# ALLModule_v1_0_2025-04-21.net
KiCad netlist of a schematic drawn in EasyEDA Pro
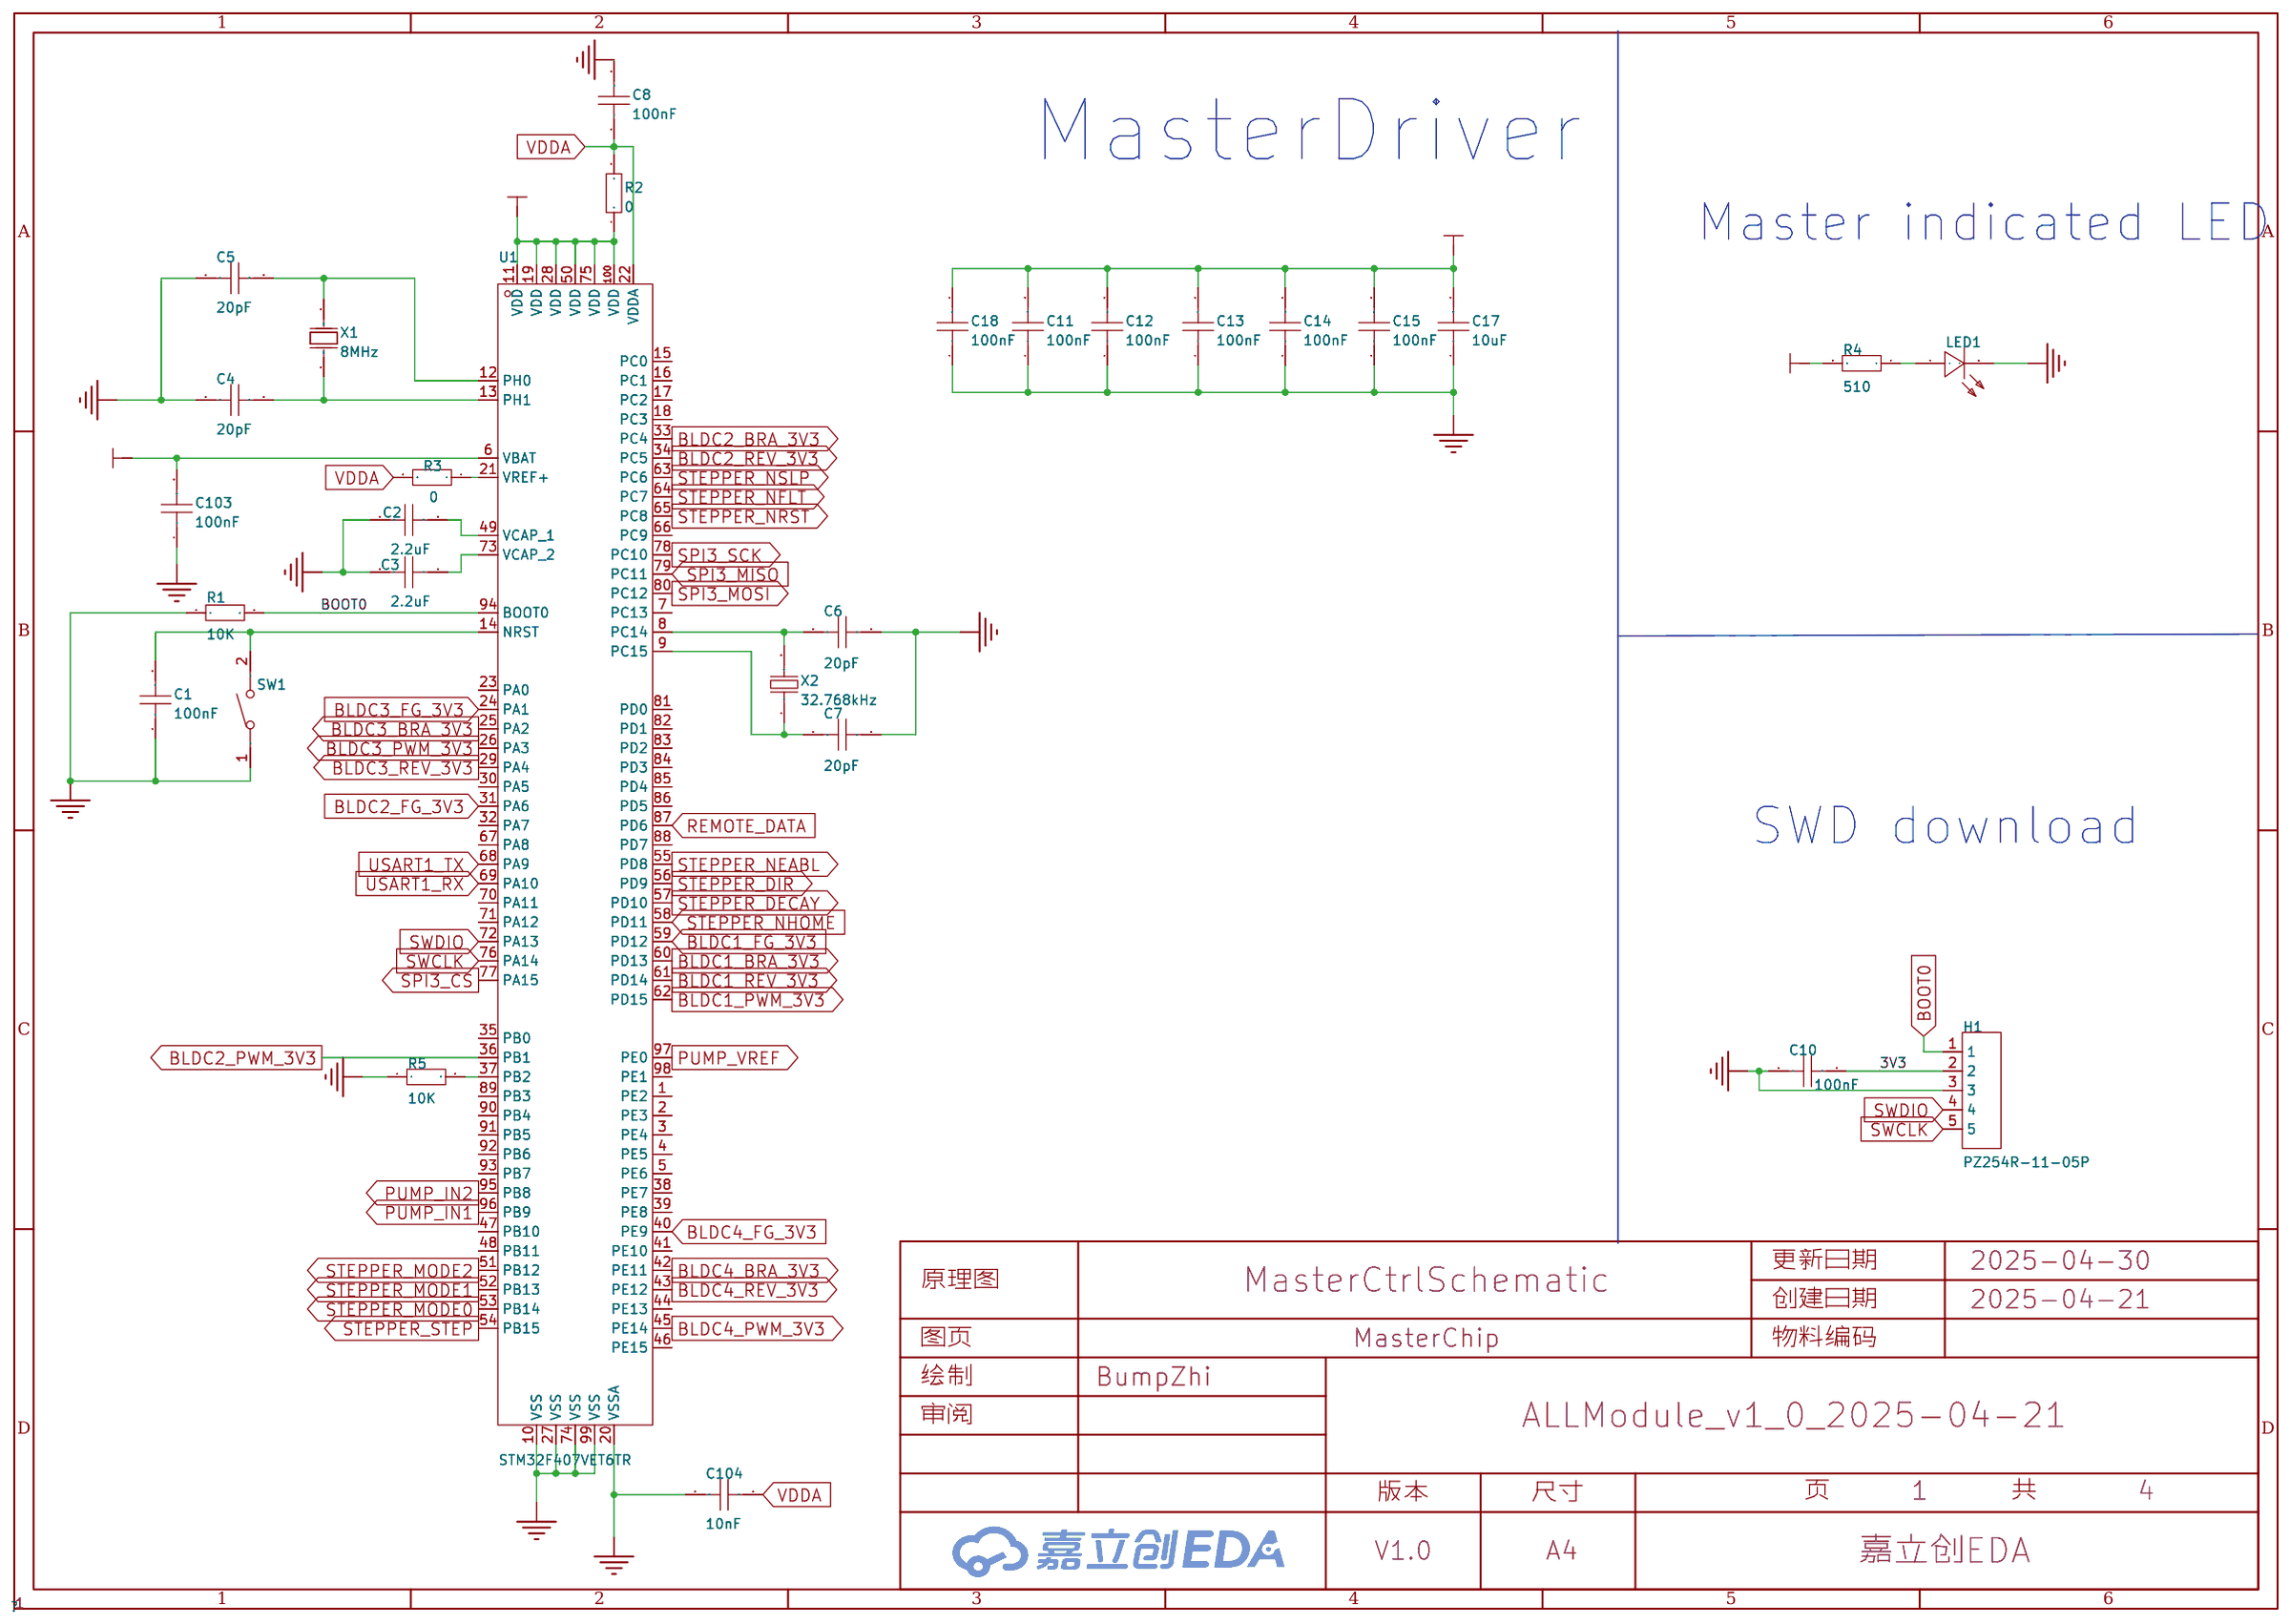
[diagram p0: MasterChip]
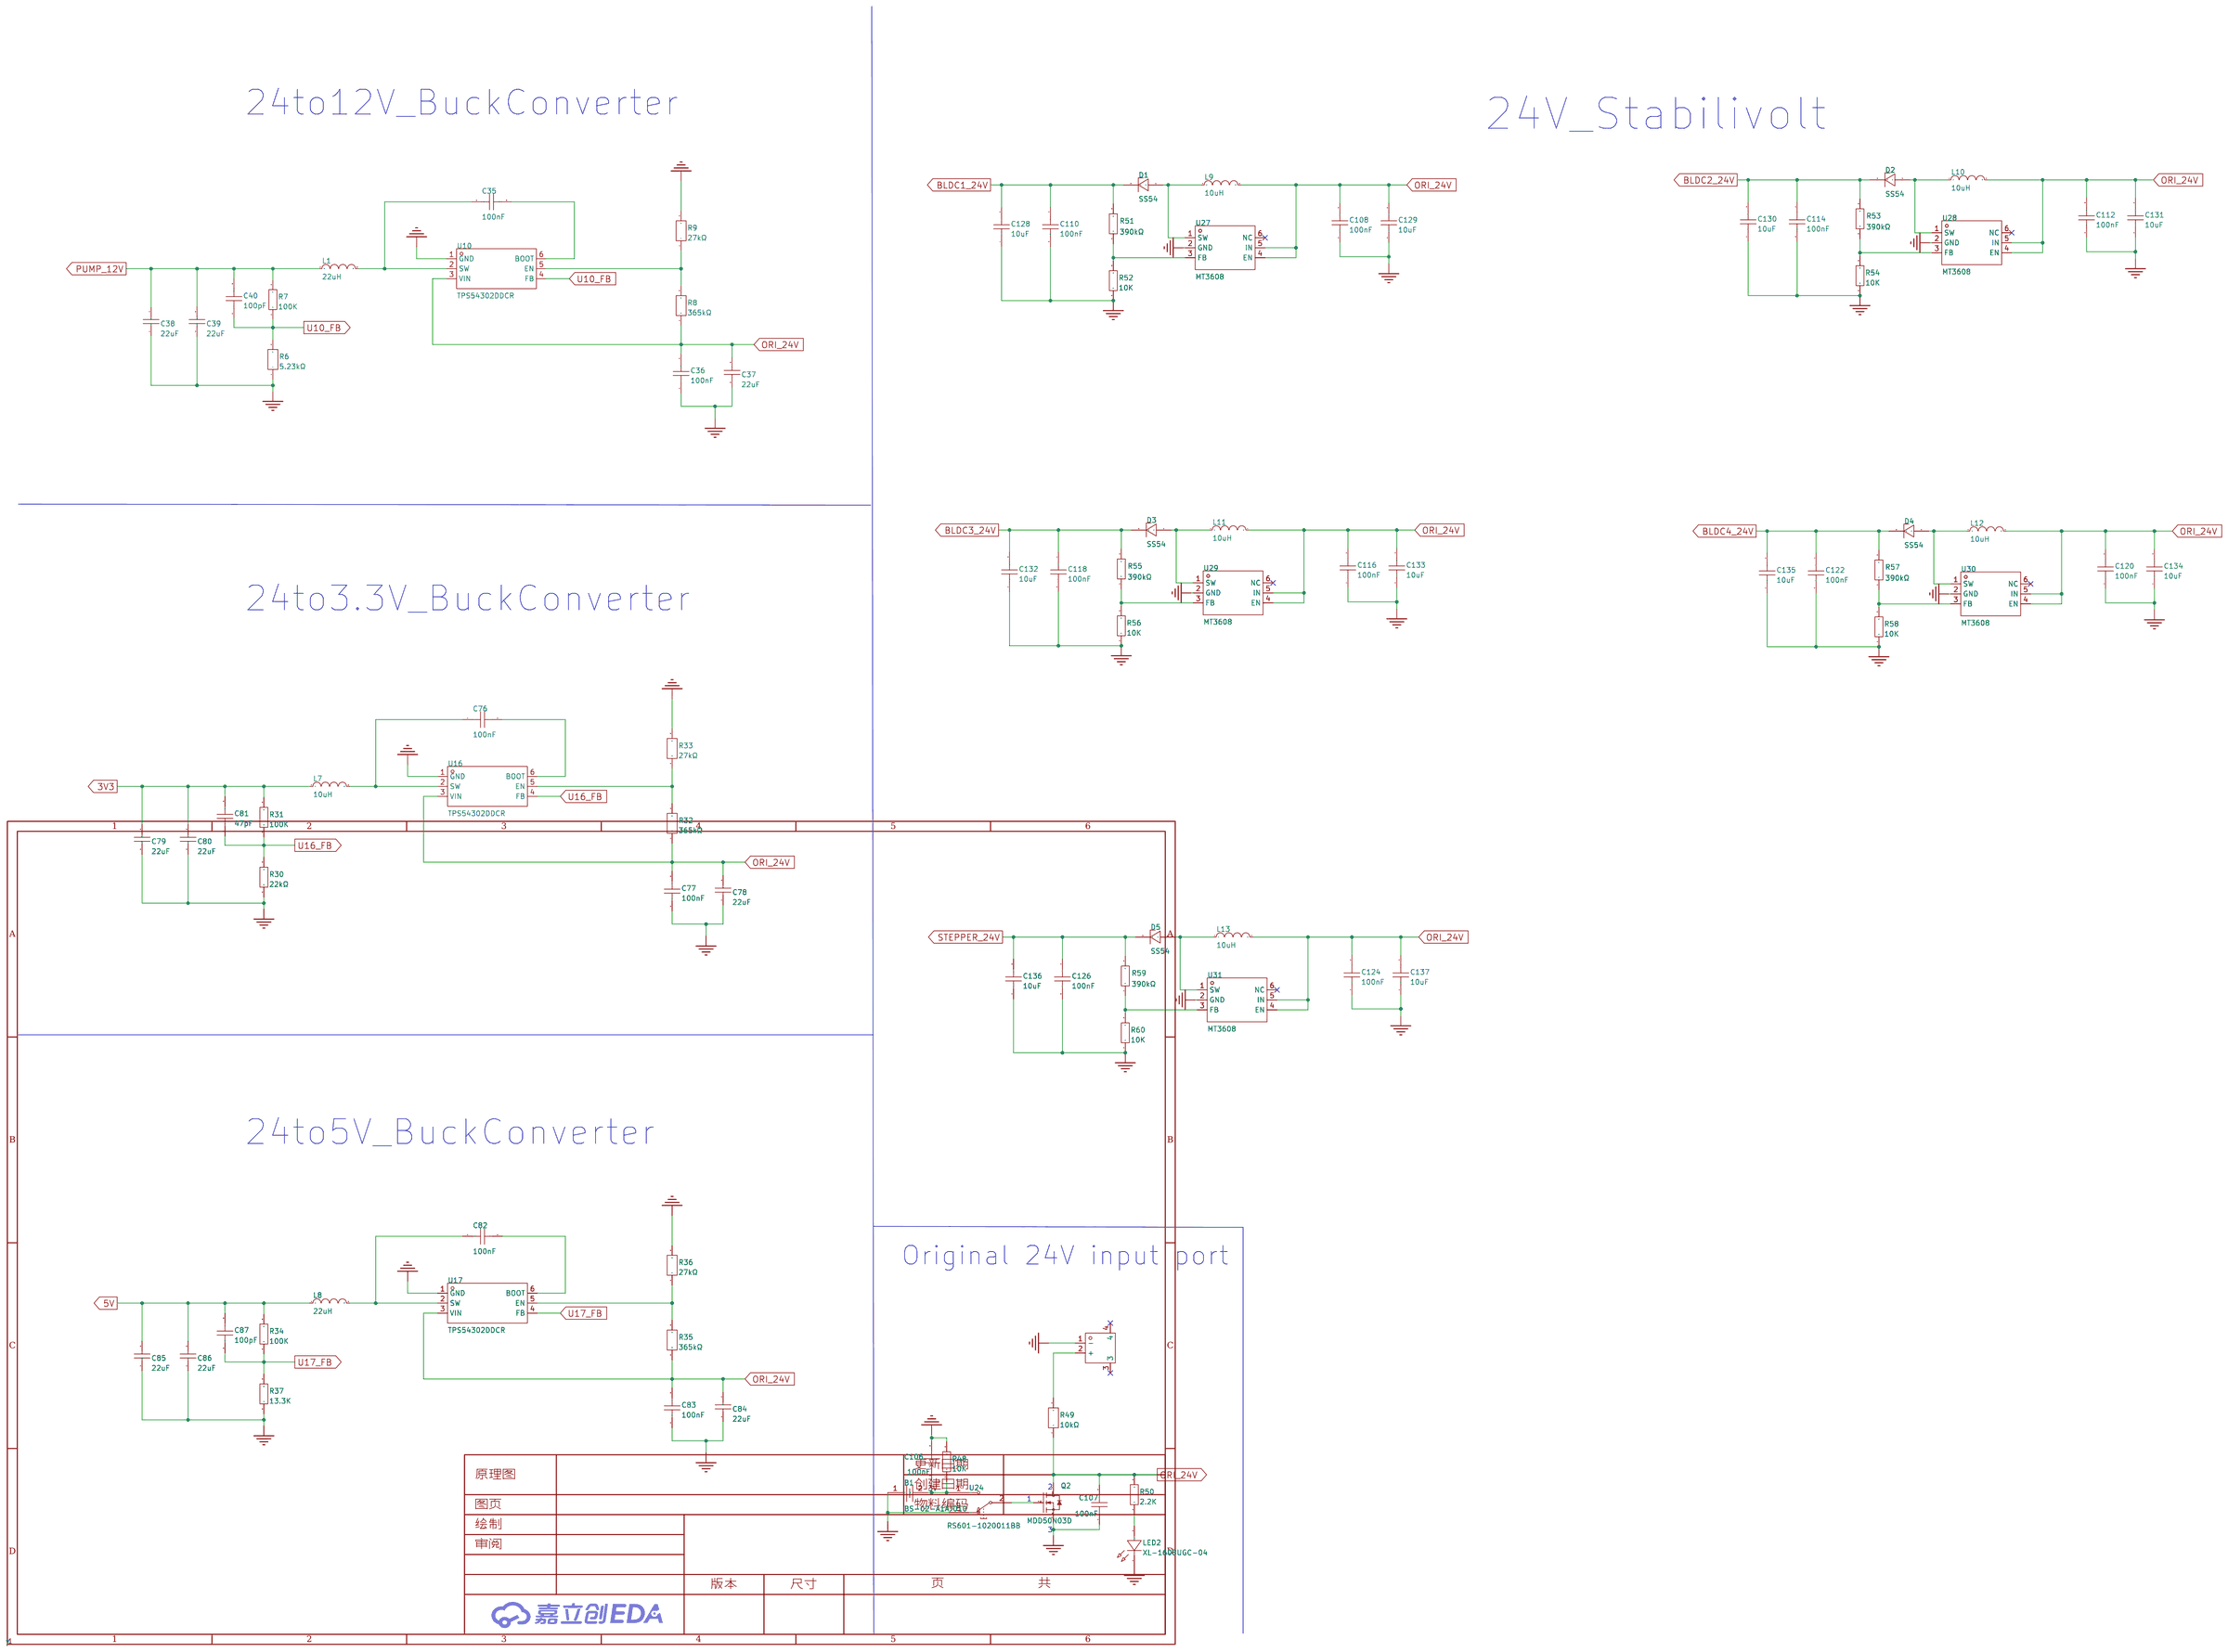
[diagram p1: PowerCtrl]
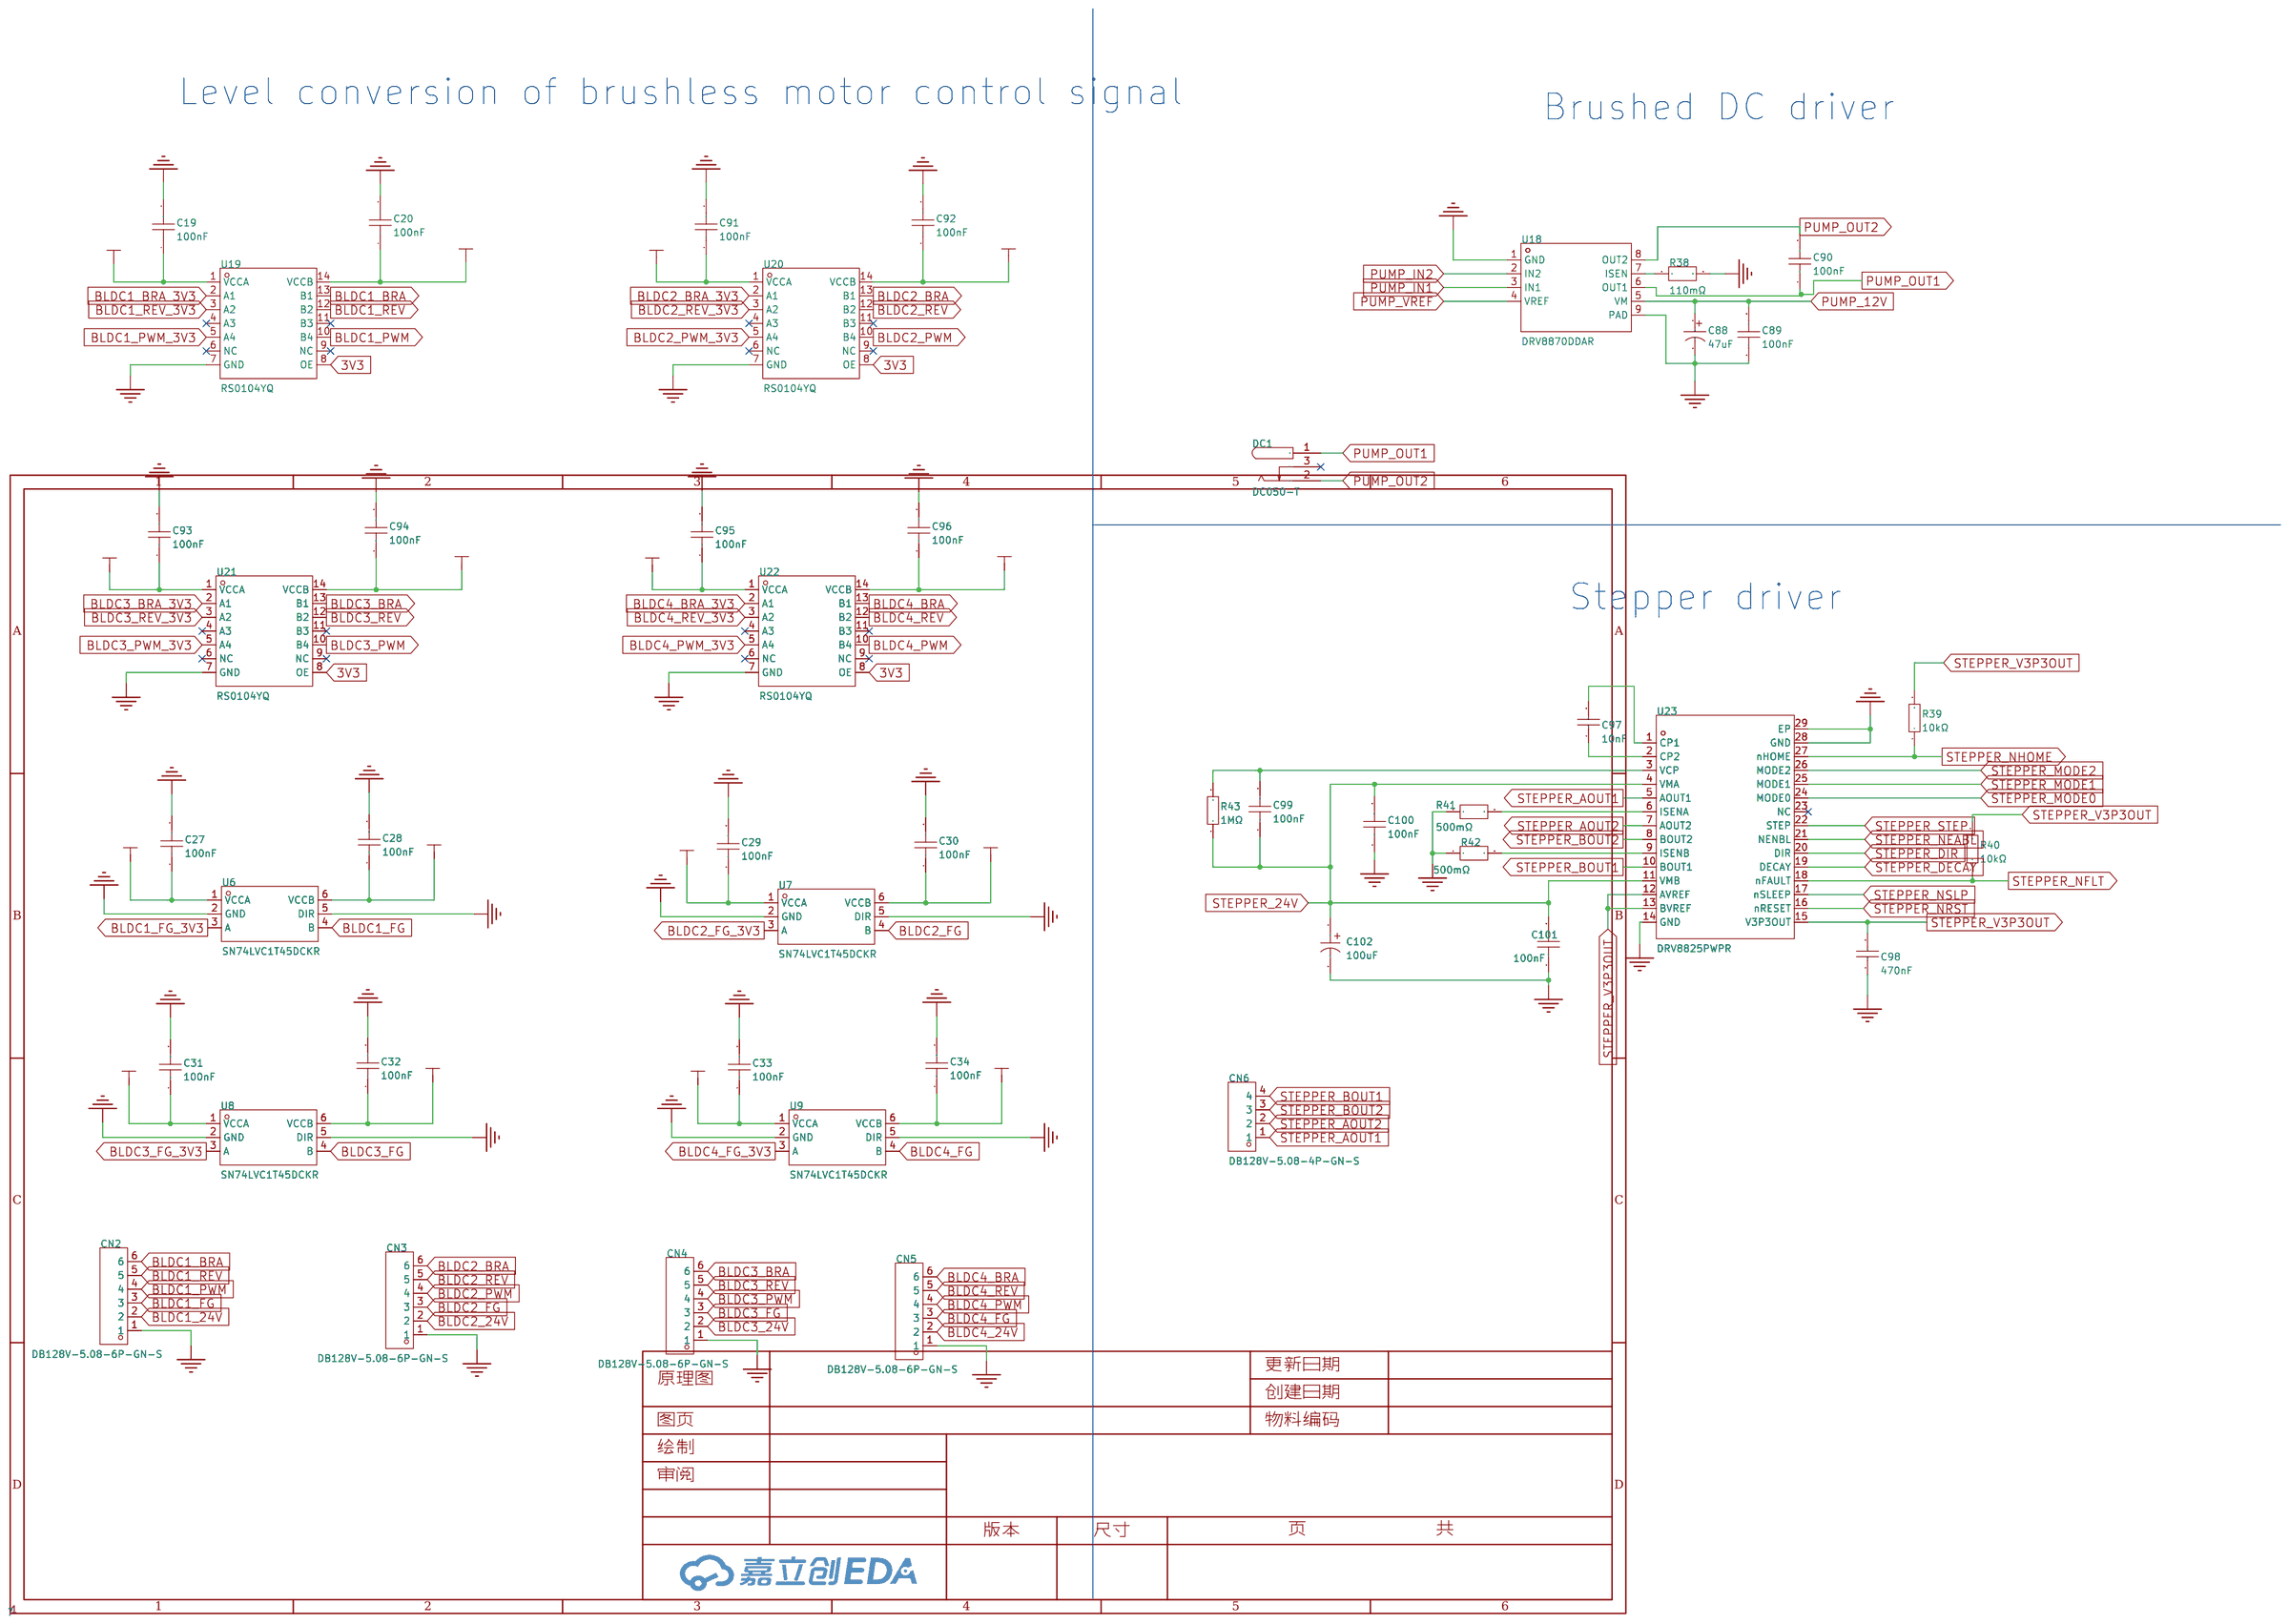
[diagram p2: MotorCtrl]
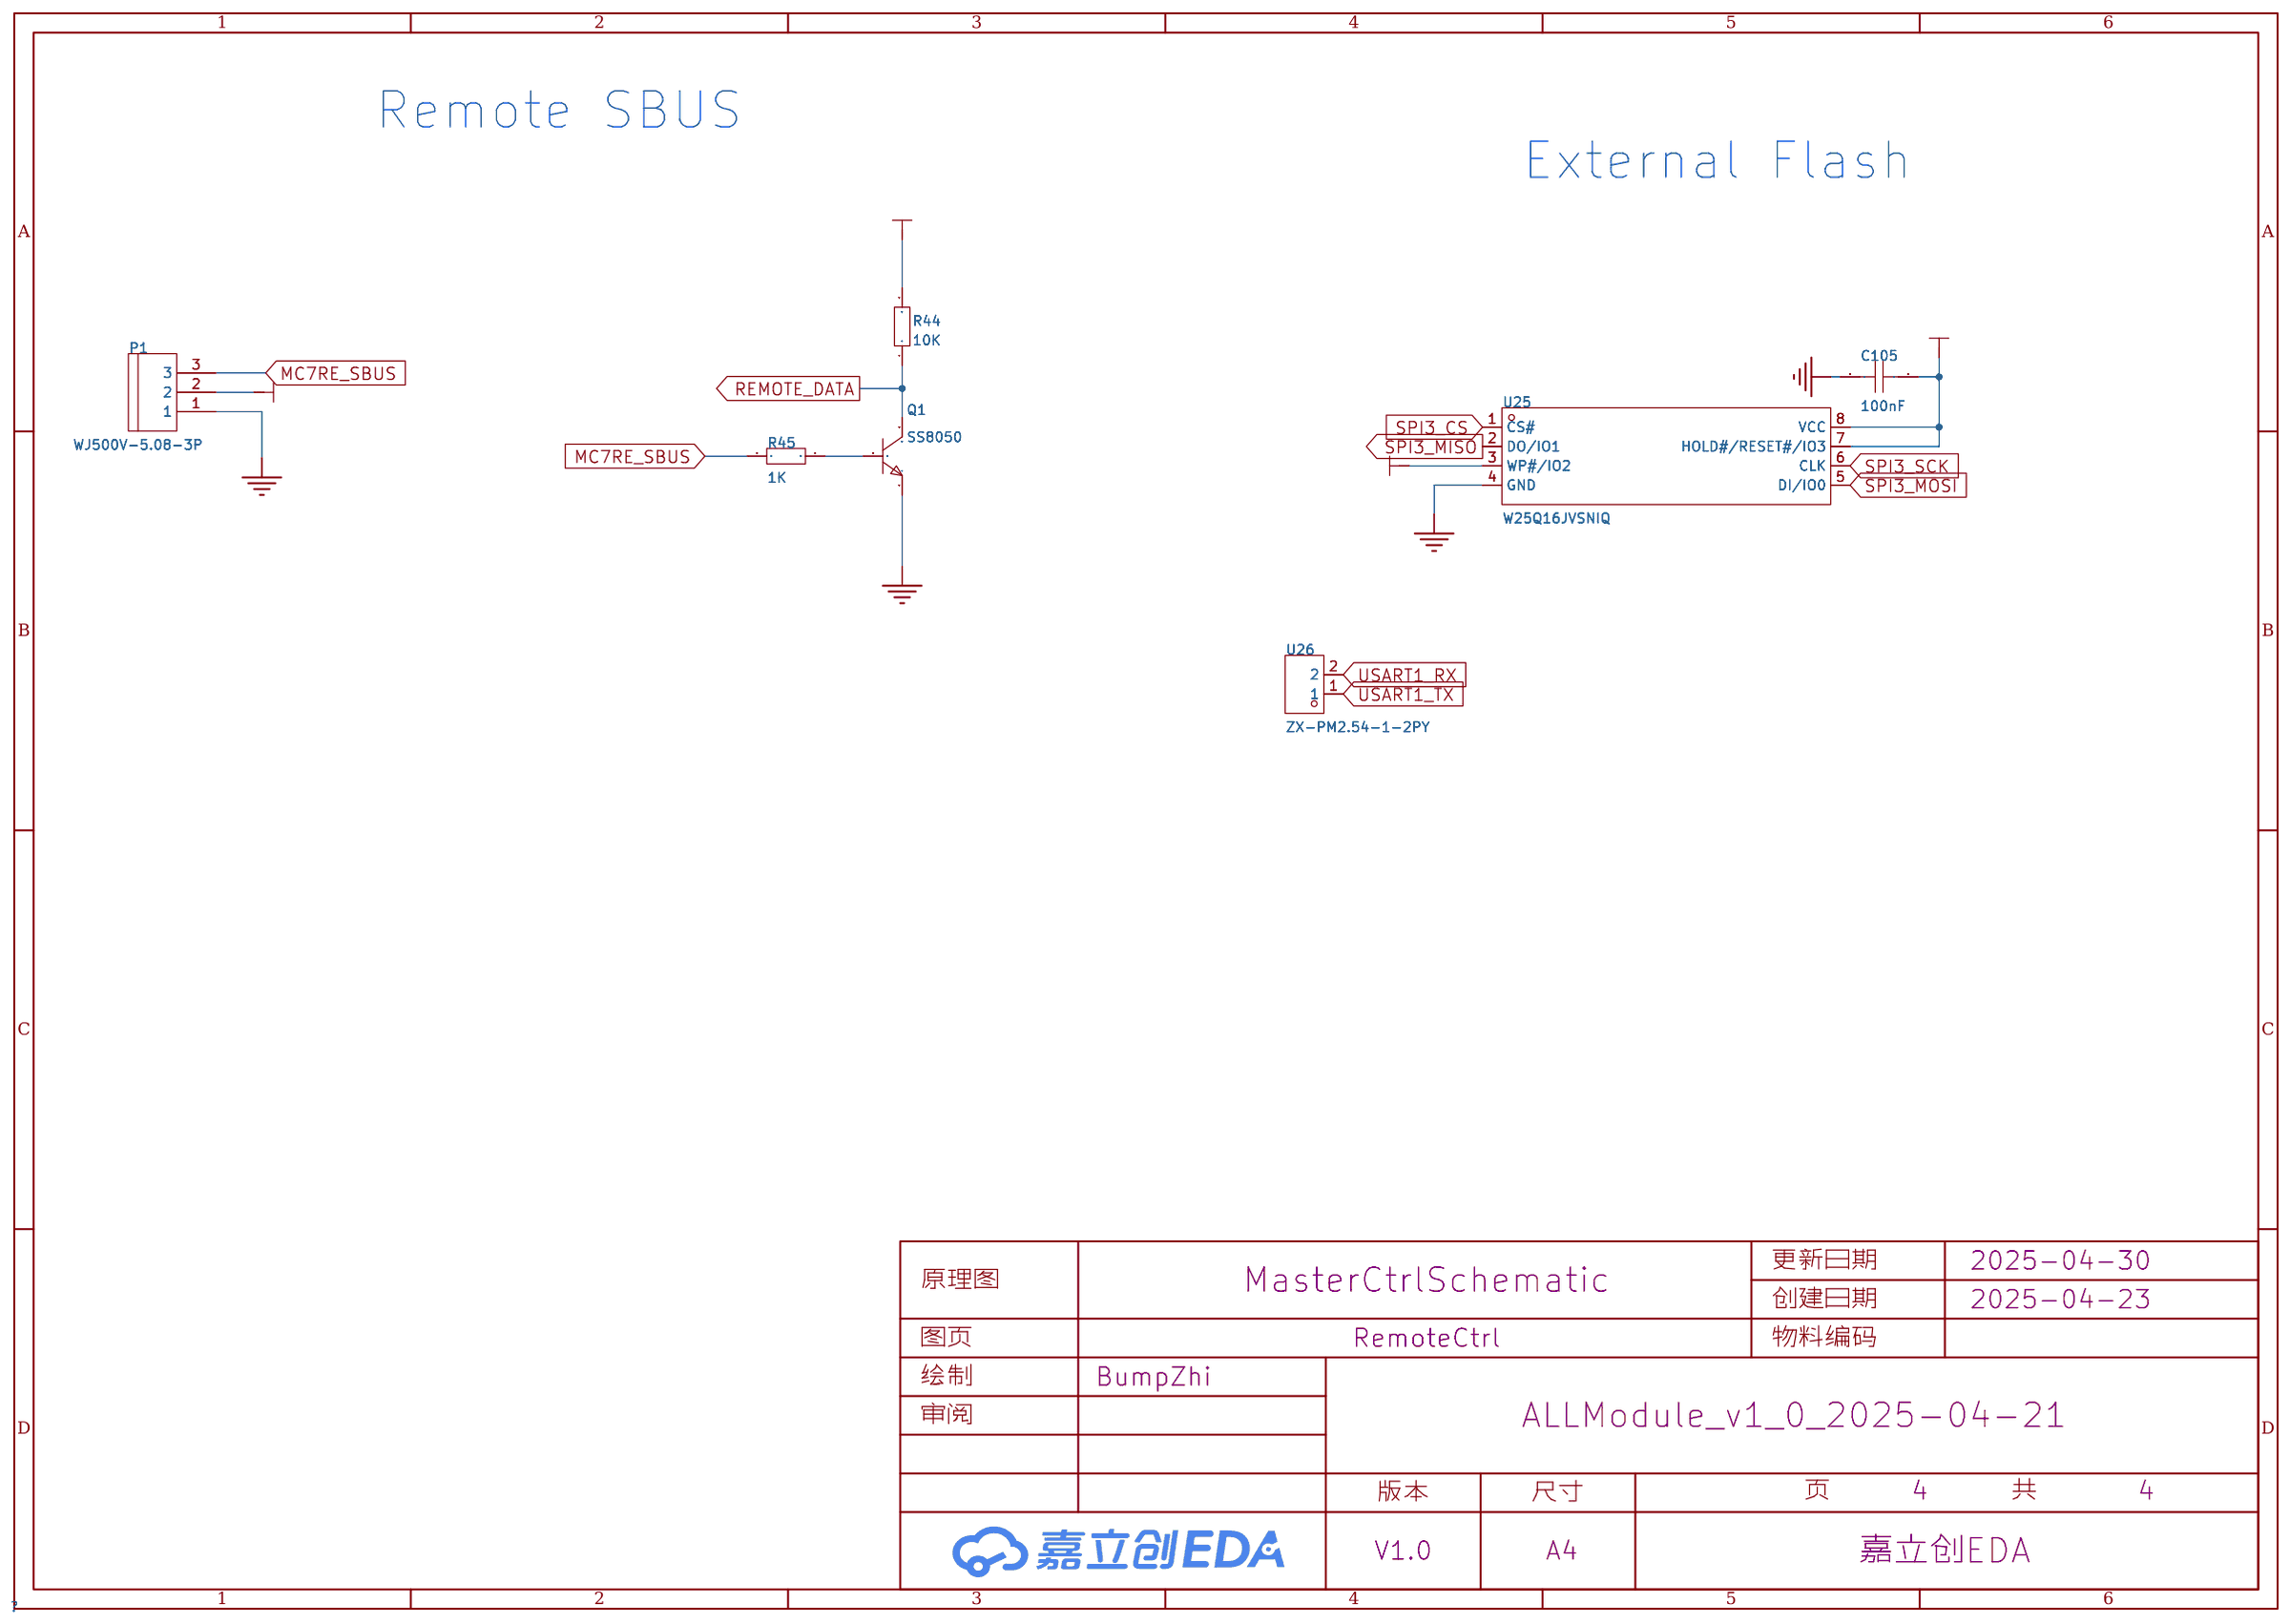
[diagram p3: RemoteCtrl]

(export (version "E")
  (design (tool "Eeschema 10.0.6"))
  (components
    (comp (ref "C1")
      (value "100nF")
      (footprint "easyedapro:C0603")
      (libsource (lib "easyedapro") (part "CapAcitance"))
    )
    (comp (ref "C2")
      (value "2.2uF")
      (footprint "easyedapro:C0603")
      (libsource (lib "easyedapro") (part "CapAcitance"))
    )
    (comp (ref "C3")
      (value "2.2uF")
      (footprint "easyedapro:C0603")
      (libsource (lib "easyedapro") (part "CapAcitance"))
    )
    (comp (ref "C4")
      (value "20pF")
      (footprint "easyedapro:C0603")
      (libsource (lib "easyedapro") (part "CapAcitance"))
    )
    (comp (ref "C5")
      (value "20pF")
      (footprint "easyedapro:C0603")
      (libsource (lib "easyedapro") (part "CapAcitance"))
    )
    (comp (ref "C6")
      (value "20pF")
      (footprint "easyedapro:C0603")
      (libsource (lib "easyedapro") (part "CapAcitance"))
    )
    (comp (ref "C7")
      (value "20pF")
      (footprint "easyedapro:C0603")
      (libsource (lib "easyedapro") (part "CapAcitance"))
    )
    (comp (ref "C8")
      (value "100nF")
      (footprint "easyedapro:C0603")
      (libsource (lib "easyedapro") (part "CapAcitance"))
    )
    (comp (ref "C10")
      (value "100nF")
      (footprint "easyedapro:C0603")
      (libsource (lib "easyedapro") (part "CapAcitance"))
    )
    (comp (ref "C11")
      (value "100nF")
      (footprint "easyedapro:C0603")
      (libsource (lib "easyedapro") (part "CapAcitance"))
    )
    (comp (ref "C12")
      (value "100nF")
      (footprint "easyedapro:C0603")
      (libsource (lib "easyedapro") (part "CapAcitance"))
    )
    (comp (ref "C13")
      (value "100nF")
      (footprint "easyedapro:C0603")
      (libsource (lib "easyedapro") (part "CapAcitance"))
    )
    (comp (ref "C14")
      (value "100nF")
      (footprint "easyedapro:C0603")
      (libsource (lib "easyedapro") (part "CapAcitance"))
    )
    (comp (ref "C15")
      (value "100nF")
      (footprint "easyedapro:C0603")
      (libsource (lib "easyedapro") (part "CapAcitance"))
    )
    (comp (ref "C17")
      (value "10uF")
      (footprint "easyedapro:C0603")
      (libsource (lib "easyedapro") (part "CapAcitance"))
    )
    (comp (ref "C18")
      (value "100nF")
      (footprint "easyedapro:C0603")
      (libsource (lib "easyedapro") (part "CapAcitance"))
    )
    (comp (ref "C103")
      (value "100nF")
      (footprint "easyedapro:C0603")
      (libsource (lib "easyedapro") (part "CapAcitance"))
    )
    (comp (ref "C104")
      (value "10nF")
      (footprint "easyedapro:C0603")
      (libsource (lib "easyedapro") (part "CapAcitance"))
    )
    (comp (ref "H1")
      (value "PZ254R-11-05P")
      (footprint "easyedapro:HDR-TH_5P-P2.54-H-M-W10.4")
      (fields (field (name "Manufacturer") "XFCN(兴飞)"))
      (libsource (lib "easyedapro") (part "PZ254R-11-05P"))
    )
    (comp (ref "LED1")
      (value "SZYY0805R")
      (footprint "easyedapro:LED0805-R-RD")
      (fields (field (name "Manufacturer") "yongyu(永裕光电)"))
      (libsource (lib "easyedapro") (part "SZYY0805R"))
    )
    (comp (ref "R1") (value "10K") (footprint "easyedapro:R0603") (libsource (lib "easyedapro") (part "电阻")))
    (comp (ref "R2") (value "0") (footprint "easyedapro:R0603") (libsource (lib "easyedapro") (part "电阻")))
    (comp (ref "R3") (value "0") (footprint "easyedapro:R0603") (libsource (lib "easyedapro") (part "电阻")))
    (comp (ref "R4") (value "510") (footprint "easyedapro:R0603") (libsource (lib "easyedapro") (part "电阻")))
    (comp (ref "R5") (value "10K") (footprint "easyedapro:R0603") (libsource (lib "easyedapro") (part "电阻")))
    (comp (ref "SW1")
      (value "TS-1088-AR02016")
      (footprint "easyedapro:SW-SMD_L3.9-W3.0-P4.45")
      (fields (field (name "Manufacturer") "XUNPU(讯普)"))
      (libsource (lib "easyedapro") (part "TS-1088-AR02016"))
    )
    (comp (ref "U1")
      (value "STM32F407VET6TR")
      (footprint "easyedapro:LQFP-100_L14.0-W14.0-P0.50-LS16.0-BL")
      (description "CPU内核:ARM-M4;CPU最大主频:168MHz;应用领域:-;")
      (fields (field (name "Manufacturer") "ST(意法半导体)"))
      (libsource (lib "easyedapro") (part "STM32F407VET6TR"))
    )
    (comp (ref "X1")
      (value "8MHz")
      (footprint "easyedapro:CRYSTAL-SMD_L11.5-W4.8-LS12.7")
      (description "晶振类型:贴片晶振;频率:8MHz;常温频差:±20ppm;外接负载电容:20pF;频率稳定度(全温):±30ppm;")
      (fields (field (name "Manufacturer Part") "X49SM8MSD2SC") (field (name "Manufacturer") "YXC(扬兴晶振)"))
      (libsource (lib "easyedapro") (part "X49SM8MSD2SC"))
    )
    (comp (ref "X2")
      (value "32.768kHz")
      (footprint "easyedapro:FC-135R_L3.2-W1.5")
      (description "晶振类型:贴片晶振;频率:32.768kHz;常温频差:±20ppm;负载电容:12.5pF;")
      (fields (field (name "Manufacturer Part") "Q13FC13500004") (field (name "Manufacturer") "EPSON(爱普生)"))
      (libsource (lib "easyedapro") (part "Q13FC1350000400"))
    )
    (comp (ref "B1")
      (value "BS-02-A1AJ010")
      (footprint "easyedapro:BAT-TH_BS-02-A1AJ010")
      (description "连接器类型:电池底座;适用电池规格:CR2032;触头材质:磷青铜;触点电镀:镍;工作温度范围:-25°C~+85°C;")
      (fields (field (name "Manufacturer") "MYOUNG(美阳)"))
      (libsource (lib "easyedapro") (part "BS-02-A1AJ010"))
    )
    (comp (ref "C35")
      (value "100nF")
      (footprint "easyedapro:C0603")
      (libsource (lib "easyedapro") (part "CapAcitance"))
    )
    (comp (ref "C36")
      (value "100nF")
      (footprint "easyedapro:C0603")
      (libsource (lib "easyedapro") (part "CapAcitance"))
    )
    (comp (ref "C37")
      (value "22uF")
      (footprint "easyedapro:C1206")
      (description "容值:22uF;精度:±10%;额定电压:25V;材质(温度系数):X5R;")
      (fields
        (field (name "Manufacturer Part") "CL31A226KAHNNNE")
        (field (name "Manufacturer") "SAMSUNG(三星)")
      )
      (libsource (lib "easyedapro") (part "CL31A226KAHNNNE"))
    )
    (comp (ref "C38")
      (value "22uF")
      (footprint "easyedapro:C1206")
      (description "容值:22uF;精度:±10%;额定电压:25V;材质(温度系数):X5R;")
      (fields
        (field (name "Manufacturer Part") "CL31A226KAHNNNE")
        (field (name "Manufacturer") "SAMSUNG(三星)")
      )
      (libsource (lib "easyedapro") (part "CL31A226KAHNNNE"))
    )
    (comp (ref "C39")
      (value "22uF")
      (footprint "easyedapro:C1206")
      (description "容值:22uF;精度:±10%;额定电压:25V;材质(温度系数):X5R;")
      (fields
        (field (name "Manufacturer Part") "CL31A226KAHNNNE")
        (field (name "Manufacturer") "SAMSUNG(三星)")
      )
      (libsource (lib "easyedapro") (part "CL31A226KAHNNNE"))
    )
    (comp (ref "C40")
      (value "100pF")
      (footprint "easyedapro:C0603")
      (description "容值:100pF;精度:±5%;额定电压:50V;材质(温度系数):NP0;")
      (fields
        (field (name "Manufacturer Part") "CC0603JRNPO9BN101")
        (field (name "Manufacturer") "YAGEO(国巨)")
      )
      (libsource (lib "easyedapro") (part "CC0603JRNPO9BN101"))
    )
    (comp (ref "C76")
      (value "100nF")
      (footprint "easyedapro:C0603")
      (libsource (lib "easyedapro") (part "CapAcitance"))
    )
    (comp (ref "C77")
      (value "100nF")
      (footprint "easyedapro:C0603")
      (libsource (lib "easyedapro") (part "CapAcitance"))
    )
    (comp (ref "C78")
      (value "22uF")
      (footprint "easyedapro:C1206")
      (description "容值:22uF;精度:±10%;额定电压:25V;材质(温度系数):X5R;")
      (fields
        (field (name "Manufacturer Part") "CL31A226KAHNNNE")
        (field (name "Manufacturer") "SAMSUNG(三星)")
      )
      (libsource (lib "easyedapro") (part "CL31A226KAHNNNE"))
    )
    (comp (ref "C79")
      (value "22uF")
      (footprint "easyedapro:C1206")
      (description "容值:22uF;精度:±10%;额定电压:25V;材质(温度系数):X5R;")
      (fields
        (field (name "Manufacturer Part") "CL31A226KAHNNNE")
        (field (name "Manufacturer") "SAMSUNG(三星)")
      )
      (libsource (lib "easyedapro") (part "CL31A226KAHNNNE"))
    )
    (comp (ref "C80")
      (value "22uF")
      (footprint "easyedapro:C1206")
      (description "容值:22uF;精度:±10%;额定电压:25V;材质(温度系数):X5R;")
      (fields
        (field (name "Manufacturer Part") "CL31A226KAHNNNE")
        (field (name "Manufacturer") "SAMSUNG(三星)")
      )
      (libsource (lib "easyedapro") (part "CL31A226KAHNNNE"))
    )
    (comp (ref "C81")
      (value "47pF")
      (footprint "easyedapro:C0603")
      (description "容值:100pF;精度:±5%;额定电压:50V;材质(温度系数):NP0;")
      (fields
        (field (name "Manufacturer Part") "CC0603JRNPO9BN101")
        (field (name "Manufacturer") "YAGEO(国巨)")
      )
      (libsource (lib "easyedapro") (part "CC0603JRNPO9BN101"))
    )
    (comp (ref "C82")
      (value "100nF")
      (footprint "easyedapro:C0603")
      (libsource (lib "easyedapro") (part "CapAcitance"))
    )
    (comp (ref "C83")
      (value "100nF")
      (footprint "easyedapro:C0603")
      (libsource (lib "easyedapro") (part "CapAcitance"))
    )
    (comp (ref "C84")
      (value "22uF")
      (footprint "easyedapro:C1206")
      (description "容值:22uF;精度:±10%;额定电压:25V;材质(温度系数):X5R;")
      (fields
        (field (name "Manufacturer Part") "CL31A226KAHNNNE")
        (field (name "Manufacturer") "SAMSUNG(三星)")
      )
      (libsource (lib "easyedapro") (part "CL31A226KAHNNNE"))
    )
    (comp (ref "C85")
      (value "22uF")
      (footprint "easyedapro:C1206")
      (description "容值:22uF;精度:±10%;额定电压:25V;材质(温度系数):X5R;")
      (fields
        (field (name "Manufacturer Part") "CL31A226KAHNNNE")
        (field (name "Manufacturer") "SAMSUNG(三星)")
      )
      (libsource (lib "easyedapro") (part "CL31A226KAHNNNE"))
    )
    (comp (ref "C86")
      (value "22uF")
      (footprint "easyedapro:C1206")
      (description "容值:22uF;精度:±10%;额定电压:25V;材质(温度系数):X5R;")
      (fields
        (field (name "Manufacturer Part") "CL31A226KAHNNNE")
        (field (name "Manufacturer") "SAMSUNG(三星)")
      )
      (libsource (lib "easyedapro") (part "CL31A226KAHNNNE"))
    )
    (comp (ref "C87")
      (value "100pF")
      (footprint "easyedapro:C0603")
      (description "容值:100pF;精度:±5%;额定电压:50V;材质(温度系数):NP0;")
      (fields
        (field (name "Manufacturer Part") "CC0603JRNPO9BN101")
        (field (name "Manufacturer") "YAGEO(国巨)")
      )
      (libsource (lib "easyedapro") (part "CC0603JRNPO9BN101"))
    )
    (comp (ref "C106")
      (value "100nF")
      (footprint "easyedapro:C0603")
      (libsource (lib "easyedapro") (part "CapAcitance"))
    )
    (comp (ref "C107")
      (value "100nF")
      (footprint "easyedapro:C0603")
      (libsource (lib "easyedapro") (part "CapAcitance"))
    )
    (comp (ref "C108")
      (value "100nF")
      (footprint "easyedapro:C0603")
      (libsource (lib "easyedapro") (part "CapAcitance"))
    )
    (comp (ref "C110")
      (value "100nF")
      (footprint "easyedapro:C0603")
      (libsource (lib "easyedapro") (part "CapAcitance"))
    )
    (comp (ref "C112")
      (value "100nF")
      (footprint "easyedapro:C0603")
      (libsource (lib "easyedapro") (part "CapAcitance"))
    )
    (comp (ref "C114")
      (value "100nF")
      (footprint "easyedapro:C0603")
      (libsource (lib "easyedapro") (part "CapAcitance"))
    )
    (comp (ref "C116")
      (value "100nF")
      (footprint "easyedapro:C0603")
      (libsource (lib "easyedapro") (part "CapAcitance"))
    )
    (comp (ref "C118")
      (value "100nF")
      (footprint "easyedapro:C0603")
      (libsource (lib "easyedapro") (part "CapAcitance"))
    )
    (comp (ref "C120")
      (value "100nF")
      (footprint "easyedapro:C0603")
      (libsource (lib "easyedapro") (part "CapAcitance"))
    )
    (comp (ref "C122")
      (value "100nF")
      (footprint "easyedapro:C0603")
      (libsource (lib "easyedapro") (part "CapAcitance"))
    )
    (comp (ref "C124")
      (value "100nF")
      (footprint "easyedapro:C0603")
      (libsource (lib "easyedapro") (part "CapAcitance"))
    )
    (comp (ref "C126")
      (value "100nF")
      (footprint "easyedapro:C0603")
      (libsource (lib "easyedapro") (part "CapAcitance"))
    )
    (comp (ref "C128")
      (value "10uF")
      (footprint "easyedapro:C1206")
      (description "容值:10uF;精度:±10%;额定电压:50V;温度系数:X5R;")
      (fields
        (field (name "Manufacturer Part") "HGC1206R5106K500NSPJ")
        (field (name "Manufacturer") "Chinocera(华瓷)")
      )
      (libsource (lib "easyedapro") (part "HGC1206R5106K500NSPJ"))
    )
    (comp (ref "C129")
      (value "10uF")
      (footprint "easyedapro:C1206")
      (description "容值:10uF;精度:±10%;额定电压:50V;温度系数:X5R;")
      (fields
        (field (name "Manufacturer Part") "HGC1206R5106K500NSPJ")
        (field (name "Manufacturer") "Chinocera(华瓷)")
      )
      (libsource (lib "easyedapro") (part "HGC1206R5106K500NSPJ"))
    )
    (comp (ref "C130")
      (value "10uF")
      (footprint "easyedapro:C1206")
      (description "容值:10uF;精度:±10%;额定电压:50V;温度系数:X5R;")
      (fields
        (field (name "Manufacturer Part") "HGC1206R5106K500NSPJ")
        (field (name "Manufacturer") "Chinocera(华瓷)")
      )
      (libsource (lib "easyedapro") (part "HGC1206R5106K500NSPJ"))
    )
    (comp (ref "C131")
      (value "10uF")
      (footprint "easyedapro:C1206")
      (description "容值:10uF;精度:±10%;额定电压:50V;温度系数:X5R;")
      (fields
        (field (name "Manufacturer Part") "HGC1206R5106K500NSPJ")
        (field (name "Manufacturer") "Chinocera(华瓷)")
      )
      (libsource (lib "easyedapro") (part "HGC1206R5106K500NSPJ"))
    )
    (comp (ref "C132")
      (value "10uF")
      (footprint "easyedapro:C1206")
      (description "容值:10uF;精度:±10%;额定电压:50V;温度系数:X5R;")
      (fields
        (field (name "Manufacturer Part") "HGC1206R5106K500NSPJ")
        (field (name "Manufacturer") "Chinocera(华瓷)")
      )
      (libsource (lib "easyedapro") (part "HGC1206R5106K500NSPJ"))
    )
    (comp (ref "C133")
      (value "10uF")
      (footprint "easyedapro:C1206")
      (description "容值:10uF;精度:±10%;额定电压:50V;温度系数:X5R;")
      (fields
        (field (name "Manufacturer Part") "HGC1206R5106K500NSPJ")
        (field (name "Manufacturer") "Chinocera(华瓷)")
      )
      (libsource (lib "easyedapro") (part "HGC1206R5106K500NSPJ"))
    )
    (comp (ref "C134")
      (value "10uF")
      (footprint "easyedapro:C1206")
      (description "容值:10uF;精度:±10%;额定电压:50V;温度系数:X5R;")
      (fields
        (field (name "Manufacturer Part") "HGC1206R5106K500NSPJ")
        (field (name "Manufacturer") "Chinocera(华瓷)")
      )
      (libsource (lib "easyedapro") (part "HGC1206R5106K500NSPJ"))
    )
    (comp (ref "C135")
      (value "10uF")
      (footprint "easyedapro:C1206")
      (description "容值:10uF;精度:±10%;额定电压:50V;温度系数:X5R;")
      (fields
        (field (name "Manufacturer Part") "HGC1206R5106K500NSPJ")
        (field (name "Manufacturer") "Chinocera(华瓷)")
      )
      (libsource (lib "easyedapro") (part "HGC1206R5106K500NSPJ"))
    )
    (comp (ref "C136")
      (value "10uF")
      (footprint "easyedapro:C1206")
      (description "容值:10uF;精度:±10%;额定电压:50V;温度系数:X5R;")
      (fields
        (field (name "Manufacturer Part") "HGC1206R5106K500NSPJ")
        (field (name "Manufacturer") "Chinocera(华瓷)")
      )
      (libsource (lib "easyedapro") (part "HGC1206R5106K500NSPJ"))
    )
    (comp (ref "C137")
      (value "10uF")
      (footprint "easyedapro:C1206")
      (description "容值:10uF;精度:±10%;额定电压:50V;温度系数:X5R;")
      (fields
        (field (name "Manufacturer Part") "HGC1206R5106K500NSPJ")
        (field (name "Manufacturer") "Chinocera(华瓷)")
      )
      (libsource (lib "easyedapro") (part "HGC1206R5106K500NSPJ"))
    )
    (comp (ref "CN1")
      (value "XT60PW-M")
      (footprint "easyedapro:CONN-TH_XT60PW-M")
      (description "类别:-;类型1:-;")
      (fields (field (name "Manufacturer") "AMASS(艾迈斯)"))
      (libsource (lib "easyedapro") (part "XT60PW-M"))
    )
    (comp (ref "D1")
      (value "SS54")
      (footprint "easyedapro:SMA_L4.3-W2.6-LS5.0-FD")
      (description "二极管配置:独立式;正向压降(Vf):550mV@5.0A;直流反向耐压(Vr):40V;整流电流:5A;")
      (fields (field (name "Manufacturer") "宏迦橙"))
      (libsource (lib "easyedapro") (part "SS54_C7420369"))
    )
    (comp (ref "D2")
      (value "SS54")
      (footprint "easyedapro:SMA_L4.3-W2.6-LS5.0-FD")
      (description "二极管配置:独立式;正向压降(Vf):550mV@5.0A;直流反向耐压(Vr):40V;整流电流:5A;")
      (fields (field (name "Manufacturer") "宏迦橙"))
      (libsource (lib "easyedapro") (part "SS54_C7420369"))
    )
    (comp (ref "D3")
      (value "SS54")
      (footprint "easyedapro:SMA_L4.3-W2.6-LS5.0-FD")
      (description "二极管配置:独立式;正向压降(Vf):550mV@5.0A;直流反向耐压(Vr):40V;整流电流:5A;")
      (fields (field (name "Manufacturer") "宏迦橙"))
      (libsource (lib "easyedapro") (part "SS54_C7420369"))
    )
    (comp (ref "D4")
      (value "SS54")
      (footprint "easyedapro:SMA_L4.3-W2.6-LS5.0-FD")
      (description "二极管配置:独立式;正向压降(Vf):550mV@5.0A;直流反向耐压(Vr):40V;整流电流:5A;")
      (fields (field (name "Manufacturer") "宏迦橙"))
      (libsource (lib "easyedapro") (part "SS54_C7420369"))
    )
    (comp (ref "D5")
      (value "SS54")
      (footprint "easyedapro:SMA_L4.3-W2.6-LS5.0-FD")
      (description "二极管配置:独立式;正向压降(Vf):550mV@5.0A;直流反向耐压(Vr):40V;整流电流:5A;")
      (fields (field (name "Manufacturer") "宏迦橙"))
      (libsource (lib "easyedapro") (part "SS54_C7420369"))
    )
    (comp (ref "L1")
      (value "22uH")
      (footprint "easyedapro:IND-SMD_L7.0-W6.6_FXL0630")
      (description "电感值:22uH;精度:±20%;额定电流:2.5A;饱和电流(Isat):3A;类型:一体成型电感;")
      (fields (field (name "Manufacturer Part") "FXL0630-220-M") (field (name "Manufacturer") "cjiang(长江微电)"))
      (libsource (lib "easyedapro") (part "FXL0630-220-M"))
    )
    (comp (ref "L7")
      (value "10uH")
      (footprint "easyedapro:IND-SMD_L7.3-W6.8")
      (description "电感值:10uH;精度:±20%;额定电流:4.5A;饱和电流(Isat):5.5A;类型:一体成型电感;")
      (fields (field (name "Manufacturer Part") "FXL0630-100-M") (field (name "Manufacturer") "cjiang(长江微电)"))
      (libsource (lib "easyedapro") (part "FXL0630-100-M"))
    )
    (comp (ref "L8")
      (value "22uH")
      (footprint "easyedapro:IND-SMD_L7.3-W6.8")
      (description "电感值:10uH;精度:±20%;额定电流:4.5A;饱和电流(Isat):5.5A;类型:一体成型电感;")
      (fields (field (name "Manufacturer Part") "FXL0630-100-M") (field (name "Manufacturer") "cjiang(长江微电)"))
      (libsource (lib "easyedapro") (part "FXL0630-100-M"))
    )
    (comp (ref "L9")
      (value "10uH")
      (footprint "easyedapro:IND-SMD_L7.3-W6.8")
      (description "电感值:10uH;精度:±20%;额定电流:4.5A;饱和电流(Isat):5.5A;类型:一体成型电感;")
      (fields (field (name "Manufacturer Part") "FXL0630-100-M") (field (name "Manufacturer") "cjiang(长江微电)"))
      (libsource (lib "easyedapro") (part "FXL0630-100-M"))
    )
    (comp (ref "L10")
      (value "10uH")
      (footprint "easyedapro:IND-SMD_L7.3-W6.8")
      (description "电感值:10uH;精度:±20%;额定电流:4.5A;饱和电流(Isat):5.5A;类型:一体成型电感;")
      (fields (field (name "Manufacturer Part") "FXL0630-100-M") (field (name "Manufacturer") "cjiang(长江微电)"))
      (libsource (lib "easyedapro") (part "FXL0630-100-M"))
    )
    (comp (ref "L11")
      (value "10uH")
      (footprint "easyedapro:IND-SMD_L7.3-W6.8")
      (description "电感值:10uH;精度:±20%;额定电流:4.5A;饱和电流(Isat):5.5A;类型:一体成型电感;")
      (fields (field (name "Manufacturer Part") "FXL0630-100-M") (field (name "Manufacturer") "cjiang(长江微电)"))
      (libsource (lib "easyedapro") (part "FXL0630-100-M"))
    )
    (comp (ref "L12")
      (value "10uH")
      (footprint "easyedapro:IND-SMD_L7.3-W6.8")
      (description "电感值:10uH;精度:±20%;额定电流:4.5A;饱和电流(Isat):5.5A;类型:一体成型电感;")
      (fields (field (name "Manufacturer Part") "FXL0630-100-M") (field (name "Manufacturer") "cjiang(长江微电)"))
      (libsource (lib "easyedapro") (part "FXL0630-100-M"))
    )
    (comp (ref "L13")
      (value "10uH")
      (footprint "easyedapro:IND-SMD_L7.3-W6.8")
      (description "电感值:10uH;精度:±20%;额定电流:4.5A;饱和电流(Isat):5.5A;类型:一体成型电感;")
      (fields (field (name "Manufacturer Part") "FXL0630-100-M") (field (name "Manufacturer") "cjiang(长江微电)"))
      (libsource (lib "easyedapro") (part "FXL0630-100-M"))
    )
    (comp (ref "LED2")
      (value "XL-1608UGC-04")
      (footprint "easyedapro:LED0603-RD_GREEN")
      (fields (field (name "Manufacturer") "XINGLIGHT(成兴光)"))
      (libsource (lib "easyedapro") (part "XL-1608UGC-04"))
    )
    (comp (ref "Q2")
      (value "MDD50N03D")
      (footprint "easyedapro:TO-252-2_L6.6-W6.1-P4.57-LS9.9-BR-CW")
      (fields (field (name "Manufacturer") "MDD(辰达半导体)"))
      (libsource (lib "easyedapro") (part "MDD50N03D"))
    )
    (comp (ref "R6")
      (value "5.23kΩ")
      (footprint "easyedapro:R0805")
      (description "电阻类型:厚膜电阻;阻值:5.23kΩ;精度:±1%;功率:125mW;工作电压:150V;温度系数:±100ppm/°C;")
      (fields (field (name "Manufacturer Part") "FRC0805F5231TS") (field (name "Manufacturer") "FOJAN(富捷)"))
      (libsource (lib "easyedapro") (part "FRC0805F5231TS"))
    )
    (comp (ref "R7") (value "100K") (footprint "easyedapro:R0603") (libsource (lib "easyedapro") (part "电阻")))
    (comp (ref "R8")
      (value "365kΩ")
      (footprint "easyedapro:R1210")
      (description "电阻类型:厚膜电阻;阻值:365kΩ;精度:±1%;功率:500mW;最大工作电压:200V;温度系数:±100ppm/°C;")
      (fields (field (name "Manufacturer Part") "AC1210FR-07365KL") (field (name "Manufacturer") "YAGEO(国巨)"))
      (libsource (lib "easyedapro") (part "AC1210FR-07365KL"))
    )
    (comp (ref "R9")
      (value "27kΩ")
      (footprint "easyedapro:R0603")
      (description "电阻类型:厚膜电阻;阻值:27kΩ;精度:±1%;功率:100mW;工作电压:75V;温度系数:±100ppm/°C;")
      (fields (field (name "Manufacturer Part") "FRC0603F2702TS") (field (name "Manufacturer") "FOJAN(富捷)"))
      (libsource (lib "easyedapro") (part "FRC0603F2702TS"))
    )
    (comp (ref "R30")
      (value "22kΩ")
      (footprint "easyedapro:R0603")
      (description "电阻类型:厚膜电阻;阻值:22kΩ;精度:±1%;功率:100mW;最大工作电压:75V;温度系数:±100ppm/°C;")
      (fields
        (field (name "Manufacturer Part") "0603WAF2202T5E")
        (field (name "Manufacturer") "UNI-ROYAL(厚声)")
      )
      (libsource (lib "easyedapro") (part "0603WAF2202T5E"))
    )
    (comp (ref "R31")
      (value "100K")
      (footprint "easyedapro:R0603")
      (libsource (lib "easyedapro") (part "电阻"))
    )
    (comp (ref "R32")
      (value "365kΩ")
      (footprint "easyedapro:R1210")
      (description "电阻类型:厚膜电阻;阻值:365kΩ;精度:±1%;功率:500mW;最大工作电压:200V;温度系数:±100ppm/°C;")
      (fields (field (name "Manufacturer Part") "AC1210FR-07365KL") (field (name "Manufacturer") "YAGEO(国巨)"))
      (libsource (lib "easyedapro") (part "AC1210FR-07365KL"))
    )
    (comp (ref "R33")
      (value "27kΩ")
      (footprint "easyedapro:R0603")
      (description "电阻类型:厚膜电阻;阻值:27kΩ;精度:±1%;功率:100mW;工作电压:75V;温度系数:±100ppm/°C;")
      (fields (field (name "Manufacturer Part") "FRC0603F2702TS") (field (name "Manufacturer") "FOJAN(富捷)"))
      (libsource (lib "easyedapro") (part "FRC0603F2702TS"))
    )
    (comp (ref "R34")
      (value "100K")
      (footprint "easyedapro:R0603")
      (libsource (lib "easyedapro") (part "电阻"))
    )
    (comp (ref "R35")
      (value "365kΩ")
      (footprint "easyedapro:R1210")
      (description "电阻类型:厚膜电阻;阻值:365kΩ;精度:±1%;功率:500mW;最大工作电压:200V;温度系数:±100ppm/°C;")
      (fields (field (name "Manufacturer Part") "AC1210FR-07365KL") (field (name "Manufacturer") "YAGEO(国巨)"))
      (libsource (lib "easyedapro") (part "AC1210FR-07365KL"))
    )
    (comp (ref "R36")
      (value "27kΩ")
      (footprint "easyedapro:R0603")
      (description "电阻类型:厚膜电阻;阻值:27kΩ;精度:±1%;功率:100mW;工作电压:75V;温度系数:±100ppm/°C;")
      (fields (field (name "Manufacturer Part") "FRC0603F2702TS") (field (name "Manufacturer") "FOJAN(富捷)"))
      (libsource (lib "easyedapro") (part "FRC0603F2702TS"))
    )
    (comp (ref "R37")
      (value "13.3K")
      (footprint "easyedapro:R0603")
      (description "电阻类型:厚膜电阻;阻值:22kΩ;精度:±1%;功率:100mW;最大工作电压:75V;温度系数:±100ppm/°C;")
      (fields
        (field (name "Manufacturer Part") "0603WAF2202T5E")
        (field (name "Manufacturer") "UNI-ROYAL(厚声)")
      )
      (libsource (lib "easyedapro") (part "0603WAF2202T5E"))
    )
    (comp (ref "R48") (value "10K") (footprint "easyedapro:R0603") (libsource (lib "easyedapro") (part "电阻")))
    (comp (ref "R49")
      (value "10kΩ")
      (footprint "easyedapro:R1206")
      (description "电阻类型:厚膜电阻;阻值:10kΩ;精度:±5%;功率:250mW;最大工作电压:200V;温度系数:±100ppm/°C;")
      (fields (field (name "Manufacturer Part") "FRC1206J103 TS") (field (name "Manufacturer") "FOJAN(富捷)"))
      (libsource (lib "easyedapro") (part "FRC1206J103 TS"))
    )
    (comp (ref "R50")
      (value "2.2K")
      (footprint "easyedapro:R0603")
      (libsource (lib "easyedapro") (part "电阻"))
    )
    (comp (ref "R51")
      (value "390kΩ")
      (footprint "easyedapro:R0603")
      (description "电阻类型:厚膜电阻;阻值:390kΩ;精度:±1%;功率:100mW;最大工作电压:75V;温度系数:±100ppm/°C;")
      (fields (field (name "Manufacturer Part") "RC0603FR-07390KL") (field (name "Manufacturer") "YAGEO(国巨)"))
      (libsource (lib "easyedapro") (part "RC0603FR-07390KL"))
    )
    (comp (ref "R52") (value "10K") (footprint "easyedapro:R0603") (libsource (lib "easyedapro") (part "电阻")))
    (comp (ref "R53")
      (value "390kΩ")
      (footprint "easyedapro:R0603")
      (description "电阻类型:厚膜电阻;阻值:390kΩ;精度:±1%;功率:100mW;最大工作电压:75V;温度系数:±100ppm/°C;")
      (fields (field (name "Manufacturer Part") "RC0603FR-07390KL") (field (name "Manufacturer") "YAGEO(国巨)"))
      (libsource (lib "easyedapro") (part "RC0603FR-07390KL"))
    )
    (comp (ref "R54") (value "10K") (footprint "easyedapro:R0603") (libsource (lib "easyedapro") (part "电阻")))
    (comp (ref "R55")
      (value "390kΩ")
      (footprint "easyedapro:R0603")
      (description "电阻类型:厚膜电阻;阻值:390kΩ;精度:±1%;功率:100mW;最大工作电压:75V;温度系数:±100ppm/°C;")
      (fields (field (name "Manufacturer Part") "RC0603FR-07390KL") (field (name "Manufacturer") "YAGEO(国巨)"))
      (libsource (lib "easyedapro") (part "RC0603FR-07390KL"))
    )
    (comp (ref "R56") (value "10K") (footprint "easyedapro:R0603") (libsource (lib "easyedapro") (part "电阻")))
    (comp (ref "R57")
      (value "390kΩ")
      (footprint "easyedapro:R0603")
      (description "电阻类型:厚膜电阻;阻值:390kΩ;精度:±1%;功率:100mW;最大工作电压:75V;温度系数:±100ppm/°C;")
      (fields (field (name "Manufacturer Part") "RC0603FR-07390KL") (field (name "Manufacturer") "YAGEO(国巨)"))
      (libsource (lib "easyedapro") (part "RC0603FR-07390KL"))
    )
    (comp (ref "R58") (value "10K") (footprint "easyedapro:R0603") (libsource (lib "easyedapro") (part "电阻")))
    (comp (ref "R59")
      (value "390kΩ")
      (footprint "easyedapro:R0603")
      (description "电阻类型:厚膜电阻;阻值:390kΩ;精度:±1%;功率:100mW;最大工作电压:75V;温度系数:±100ppm/°C;")
      (fields (field (name "Manufacturer Part") "RC0603FR-07390KL") (field (name "Manufacturer") "YAGEO(国巨)"))
      (libsource (lib "easyedapro") (part "RC0603FR-07390KL"))
    )
    (comp (ref "R60") (value "10K") (footprint "easyedapro:R0603") (libsource (lib "easyedapro") (part "电阻")))
    (comp (ref "U10")
      (value "TPS54302DDCR")
      (footprint "easyedapro:SOT-23-6_L2.9-W1.6-P0.95-LS2.8-BL")
      (description "功能类型:降压型;输出类型:固定;工作电压:4.5V~28V;输出电压:5V;输出电流:3A;")
      (fields (field (name "Manufacturer") "TI(德州仪器)"))
      (libsource (lib "easyedapro") (part "TPS54302DDCR_C311983"))
    )
    (comp (ref "U16")
      (value "TPS54302DDCR")
      (footprint "easyedapro:SOT-23-6_L2.9-W1.6-P0.95-LS2.8-BL")
      (description "功能类型:降压型;输出类型:固定;工作电压:4.5V~28V;输出电压:5V;输出电流:3A;")
      (fields (field (name "Manufacturer") "TI(德州仪器)"))
      (libsource (lib "easyedapro") (part "TPS54302DDCR_C311983"))
    )
    (comp (ref "U17")
      (value "TPS54302DDCR")
      (footprint "easyedapro:SOT-23-6_L2.9-W1.6-P0.95-LS2.8-BL")
      (description "功能类型:降压型;输出类型:固定;工作电压:4.5V~28V;输出电压:5V;输出电流:3A;")
      (fields (field (name "Manufacturer") "TI(德州仪器)"))
      (libsource (lib "easyedapro") (part "TPS54302DDCR_C311983"))
    )
    (comp (ref "U24")
      (value "RS601-1020011BB")
      (footprint "easyedapro:SW-TH_RS601-1020011BB")
      (description "带灯:无;引脚样式:焊片;额定电流:8A;额定电压(AC):250V;额定电压(DC):-;电路结构:单刀双掷;机械寿命:1万次;")
      (fields (field (name "Manufacturer") "HCTL(华灿天禄)"))
      (libsource (lib "easyedapro") (part "RS601-1020011BB"))
    )
    (comp (ref "U27")
      (value "MT3608")
      (footprint "easyedapro:SOT-23-6_L2.9-W1.6-P0.95-LS2.8-BL")
      (description "功能类型:升压型;输出类型:可调;工作电压:2V~24V;输出电压:28V;输出电流:2A;")
      (fields (field (name "Manufacturer") "西安航天民芯"))
      (libsource (lib "easyedapro") (part "MT3608"))
    )
    (comp (ref "U28")
      (value "MT3608")
      (footprint "easyedapro:SOT-23-6_L2.9-W1.6-P0.95-LS2.8-BL")
      (description "功能类型:升压型;输出类型:可调;工作电压:2V~24V;输出电压:28V;输出电流:2A;")
      (fields (field (name "Manufacturer") "西安航天民芯"))
      (libsource (lib "easyedapro") (part "MT3608"))
    )
    (comp (ref "U29")
      (value "MT3608")
      (footprint "easyedapro:SOT-23-6_L2.9-W1.6-P0.95-LS2.8-BL")
      (description "功能类型:升压型;输出类型:可调;工作电压:2V~24V;输出电压:28V;输出电流:2A;")
      (fields (field (name "Manufacturer") "西安航天民芯"))
      (libsource (lib "easyedapro") (part "MT3608"))
    )
    (comp (ref "U30")
      (value "MT3608")
      (footprint "easyedapro:SOT-23-6_L2.9-W1.6-P0.95-LS2.8-BL")
      (description "功能类型:升压型;输出类型:可调;工作电压:2V~24V;输出电压:28V;输出电流:2A;")
      (fields (field (name "Manufacturer") "西安航天民芯"))
      (libsource (lib "easyedapro") (part "MT3608"))
    )
    (comp (ref "U31")
      (value "MT3608")
      (footprint "easyedapro:SOT-23-6_L2.9-W1.6-P0.95-LS2.8-BL")
      (description "功能类型:升压型;输出类型:可调;工作电压:2V~24V;输出电压:28V;输出电流:2A;")
      (fields (field (name "Manufacturer") "西安航天民芯"))
      (libsource (lib "easyedapro") (part "MT3608"))
    )
    (comp (ref "C19")
      (value "100nF")
      (footprint "easyedapro:C0603")
      (libsource (lib "easyedapro") (part "CapAcitance"))
    )
    (comp (ref "C20")
      (value "100nF")
      (footprint "easyedapro:C0603")
      (libsource (lib "easyedapro") (part "CapAcitance"))
    )
    (comp (ref "C27")
      (value "100nF")
      (footprint "easyedapro:C0603")
      (libsource (lib "easyedapro") (part "CapAcitance"))
    )
    (comp (ref "C28")
      (value "100nF")
      (footprint "easyedapro:C0603")
      (libsource (lib "easyedapro") (part "CapAcitance"))
    )
    (comp (ref "C29")
      (value "100nF")
      (footprint "easyedapro:C0603")
      (libsource (lib "easyedapro") (part "CapAcitance"))
    )
    (comp (ref "C30")
      (value "100nF")
      (footprint "easyedapro:C0603")
      (libsource (lib "easyedapro") (part "CapAcitance"))
    )
    (comp (ref "C31")
      (value "100nF")
      (footprint "easyedapro:C0603")
      (libsource (lib "easyedapro") (part "CapAcitance"))
    )
    (comp (ref "C32")
      (value "100nF")
      (footprint "easyedapro:C0603")
      (libsource (lib "easyedapro") (part "CapAcitance"))
    )
    (comp (ref "C33")
      (value "100nF")
      (footprint "easyedapro:C0603")
      (libsource (lib "easyedapro") (part "CapAcitance"))
    )
    (comp (ref "C34")
      (value "100nF")
      (footprint "easyedapro:C0603")
      (libsource (lib "easyedapro") (part "CapAcitance"))
    )
    (comp (ref "C88")
      (value "47uF")
      (footprint "easyedapro:CAP-TH_BD6.3-P2.50-D1.0-FD")
      (description "容值:47uF;精度:±20%;额定电压:50V;")
      (fields
        (field (name "Manufacturer Part") "KM476M050E11RR0VH2FP0")
        (field (name "Manufacturer") "CX(承兴)")
      )
      (libsource (lib "easyedapro") (part "47uF 50V 6.3*11_C45101"))
    )
    (comp (ref "C89")
      (value "100nF")
      (footprint "easyedapro:C0603")
      (description "容值:100nF;精度:±10%;额定电压:50V;温度系数:X7R;")
      (fields
        (field (name "Manufacturer Part") "CGA0603X7R104K500JT")
        (field (name "Manufacturer") "HRE(芯声)")
      )
      (libsource (lib "easyedapro") (part "CGA0603X7R104K500JT"))
    )
    (comp (ref "C90")
      (value "100nF")
      (footprint "easyedapro:C0603")
      (description "容值:100nF;精度:±10%;额定电压:50V;温度系数:X7R;")
      (fields
        (field (name "Manufacturer Part") "CGA0603X7R104K500JT")
        (field (name "Manufacturer") "HRE(芯声)")
      )
      (libsource (lib "easyedapro") (part "CGA0603X7R104K500JT"))
    )
    (comp (ref "C91")
      (value "100nF")
      (footprint "easyedapro:C0603")
      (libsource (lib "easyedapro") (part "CapAcitance"))
    )
    (comp (ref "C92")
      (value "100nF")
      (footprint "easyedapro:C0603")
      (libsource (lib "easyedapro") (part "CapAcitance"))
    )
    (comp (ref "C93")
      (value "100nF")
      (footprint "easyedapro:C0603")
      (libsource (lib "easyedapro") (part "CapAcitance"))
    )
    (comp (ref "C94")
      (value "100nF")
      (footprint "easyedapro:C0603")
      (libsource (lib "easyedapro") (part "CapAcitance"))
    )
    (comp (ref "C95")
      (value "100nF")
      (footprint "easyedapro:C0603")
      (libsource (lib "easyedapro") (part "CapAcitance"))
    )
    (comp (ref "C96")
      (value "100nF")
      (footprint "easyedapro:C0603")
      (libsource (lib "easyedapro") (part "CapAcitance"))
    )
    (comp (ref "C97")
      (value "10nF")
      (footprint "easyedapro:C0603")
      (description "容值:10nF;精度:±10%;额定电压:50V;材质(温度系数):X7R;")
      (fields
        (field (name "Manufacturer Part") "CL10B103KB8NNNC")
        (field (name "Manufacturer") "SAMSUNG(三星)")
      )
      (libsource (lib "easyedapro") (part "CL10B103KB8NNNC"))
    )
    (comp (ref "C98")
      (value "470nF")
      (footprint "easyedapro:C0603")
      (description "容值:470nF;精度:±10%;额定电压:25V;材质(温度系数):X7R;")
      (fields
        (field (name "Manufacturer Part") "CL10B474KA8NNNC")
        (field (name "Manufacturer") "SAMSUNG(三星)")
      )
      (libsource (lib "easyedapro") (part "CL10B474KA8NNNC"))
    )
    (comp (ref "C99")
      (value "100nF")
      (footprint "easyedapro:C0603")
      (description "容值:100nF;精度:±10%;额定电压:50V;温度系数:X7R;")
      (fields
        (field (name "Manufacturer Part") "CGA0603X7R104K500JT")
        (field (name "Manufacturer") "HRE(芯声)")
      )
      (libsource (lib "easyedapro") (part "CGA0603X7R104K500JT"))
    )
    (comp (ref "C100")
      (value "100nF")
      (footprint "easyedapro:C0603")
      (description "容值:100nF;精度:±10%;额定电压:50V;温度系数:X7R;")
      (fields
        (field (name "Manufacturer Part") "CGA0603X7R104K500JT")
        (field (name "Manufacturer") "HRE(芯声)")
      )
      (libsource (lib "easyedapro") (part "CGA0603X7R104K500JT"))
    )
    (comp (ref "C101")
      (value "100nF")
      (footprint "easyedapro:C0603")
      (description "容值:100nF;精度:±10%;额定电压:50V;温度系数:X7R;")
      (fields
        (field (name "Manufacturer Part") "CGA0603X7R104K500JT")
        (field (name "Manufacturer") "HRE(芯声)")
      )
      (libsource (lib "easyedapro") (part "CGA0603X7R104K500JT"))
    )
    (comp (ref "C102")
      (value "100uF")
      (footprint "easyedapro:CAP-SMD_BD8.1-L8.3-W8.3-LS9.3-FD")
      (description "容值:100uF;精度:±20%;额定电压:50V;纹波电流:300mA@100kHz;等效串联电阻:600mΩ@100kHz;")
      (fields
        (field (name "Manufacturer Part") "GVE1H107M0810CNVC")
        (field (name "Manufacturer") "HRK(鸿瑞凯电子)")
      )
      (libsource (lib "easyedapro") (part "GVE1H107M0810CNVC"))
    )
    (comp (ref "CN2")
      (value "DB128V-5.08-6P-GN-S")
      (footprint "easyedapro:CONN-TH_6P-P5.08_DIBO_DB128V-5.08")
      (fields (field (name "Manufacturer") "DORABO(地博电气)"))
      (libsource (lib "easyedapro") (part "DB128V-5.08-6P-GN-S"))
    )
    (comp (ref "CN3")
      (value "DB128V-5.08-6P-GN-S")
      (footprint "easyedapro:CONN-TH_6P-P5.08_DIBO_DB128V-5.08")
      (fields (field (name "Manufacturer") "DORABO(地博电气)"))
      (libsource (lib "easyedapro") (part "DB128V-5.08-6P-GN-S"))
    )
    (comp (ref "CN4")
      (value "DB128V-5.08-6P-GN-S")
      (footprint "easyedapro:CONN-TH_6P-P5.08_DIBO_DB128V-5.08")
      (fields (field (name "Manufacturer") "DORABO(地博电气)"))
      (libsource (lib "easyedapro") (part "DB128V-5.08-6P-GN-S"))
    )
    (comp (ref "CN5")
      (value "DB128V-5.08-6P-GN-S")
      (footprint "easyedapro:CONN-TH_6P-P5.08_DIBO_DB128V-5.08")
      (fields (field (name "Manufacturer") "DORABO(地博电气)"))
      (libsource (lib "easyedapro") (part "DB128V-5.08-6P-GN-S"))
    )
    (comp (ref "CN6")
      (value "DB128V-5.08-4P-GN-S")
      (footprint "easyedapro:CONN-TH_4P-P5.08_DIBO_DB128V-5.08")
      (fields (field (name "Manufacturer") "DORABO(地博电气)"))
      (libsource (lib "easyedapro") (part "DB128V-5.08-4P-GN-S"))
    )
    (comp (ref "DC1")
      (value "DC050-T")
      (footprint "easyedapro:DC-IN_DC050-T")
      (description "连接器类型:DC电源插座;安装方式:卧贴;触点内径:2mm;触点外径:6.4mm;额定电流:2A;额定电压:30V;工作温度范围:-25°C~+70°C;")
      (fields (field (name "Manufacturer") "SHOU HAN(首韩)"))
      (libsource (lib "easyedapro") (part "DC050-T"))
    )
    (comp (ref "R38")
      (value "110mΩ")
      (footprint "easyedapro:R1206")
      (description "电阻类型:厚膜电阻;阻值:110mΩ;精度:±1%;功率:250mW;最大工作电压:500V;温度系数:±600ppm/°C;")
      (fields (field (name "Manufacturer Part") "FRL1206FR110TS") (field (name "Manufacturer") "FOJAN(富捷)"))
      (libsource (lib "easyedapro") (part "FRL1206FR110TS"))
    )
    (comp (ref "R39")
      (value "10kΩ")
      (footprint "easyedapro:R0603")
      (description "电阻类型:厚膜电阻;阻值:10kΩ;精度:±1%;功率:100mW;最大工作电压:75V;温度系数:±100ppm/°C;")
      (fields (field (name "Manufacturer Part") "RC0603FR-0710KL") (field (name "Manufacturer") "YAGEO(国巨)"))
      (libsource (lib "easyedapro") (part "RC0603FR-0710KL"))
    )
    (comp (ref "R40")
      (value "10kΩ")
      (footprint "easyedapro:R0603")
      (description "电阻类型:厚膜电阻;阻值:10kΩ;精度:±1%;功率:100mW;最大工作电压:75V;温度系数:±100ppm/°C;")
      (fields (field (name "Manufacturer Part") "RC0603FR-0710KL") (field (name "Manufacturer") "YAGEO(国巨)"))
      (libsource (lib "easyedapro") (part "RC0603FR-0710KL"))
    )
    (comp (ref "R41")
      (value "500mΩ")
      (footprint "easyedapro:R0603")
      (description "电阻类型:厚膜电阻;阻值:500mΩ;精度:±5%;功率:100mW;最大工作电压:100V;温度系数:±300ppm/°C;")
      (fields (field (name "Manufacturer Part") "FRL0603JR500TS") (field (name "Manufacturer") "FOJAN(富捷)"))
      (libsource (lib "easyedapro") (part "FRL0603JR500TS"))
    )
    (comp (ref "R42")
      (value "500mΩ")
      (footprint "easyedapro:R0603")
      (description "电阻类型:厚膜电阻;阻值:500mΩ;精度:±5%;功率:100mW;最大工作电压:100V;温度系数:±300ppm/°C;")
      (fields (field (name "Manufacturer Part") "FRL0603JR500TS") (field (name "Manufacturer") "FOJAN(富捷)"))
      (libsource (lib "easyedapro") (part "FRL0603JR500TS"))
    )
    (comp (ref "R43")
      (value "1MΩ")
      (footprint "easyedapro:R0603")
      (fields
        (field (name "Manufacturer Part") "0603WAF1004T5E")
        (field (name "Manufacturer") "UNI-ROYAL(厚声)")
      )
      (libsource (lib "easyedapro") (part "电阻"))
    )
    (comp (ref "U6")
      (value "SN74LVC1T45DCKR")
      (footprint "easyedapro:SC-70-6_L2.2-W1.3-P0.65-LS2.2-BR")
      (description "数据速率:420Mbps;电压(VCCA):1.65V~5.5V;电压(VCCB):1.65V~5.5V;电路数:1;每个电路通道数:1;")
      (fields (field (name "Manufacturer") "TI(德州仪器)"))
      (libsource (lib "easyedapro") (part "SN74LVC1T45DCKR"))
    )
    (comp (ref "U7")
      (value "SN74LVC1T45DCKR")
      (footprint "easyedapro:SC-70-6_L2.2-W1.3-P0.65-LS2.2-BR")
      (description "数据速率:420Mbps;电压(VCCA):1.65V~5.5V;电压(VCCB):1.65V~5.5V;电路数:1;每个电路通道数:1;")
      (fields (field (name "Manufacturer") "TI(德州仪器)"))
      (libsource (lib "easyedapro") (part "SN74LVC1T45DCKR"))
    )
    (comp (ref "U8")
      (value "SN74LVC1T45DCKR")
      (footprint "easyedapro:SC-70-6_L2.2-W1.3-P0.65-LS2.2-BR")
      (description "数据速率:420Mbps;电压(VCCA):1.65V~5.5V;电压(VCCB):1.65V~5.5V;电路数:1;每个电路通道数:1;")
      (fields (field (name "Manufacturer") "TI(德州仪器)"))
      (libsource (lib "easyedapro") (part "SN74LVC1T45DCKR"))
    )
    (comp (ref "U9")
      (value "SN74LVC1T45DCKR")
      (footprint "easyedapro:SC-70-6_L2.2-W1.3-P0.65-LS2.2-BR")
      (description "数据速率:420Mbps;电压(VCCA):1.65V~5.5V;电压(VCCB):1.65V~5.5V;电路数:1;每个电路通道数:1;")
      (fields (field (name "Manufacturer") "TI(德州仪器)"))
      (libsource (lib "easyedapro") (part "SN74LVC1T45DCKR"))
    )
    (comp (ref "U18")
      (value "DRV8870DDAR")
      (footprint "easyedapro:HSOP-8_L5.0-W4.0-P1.27-LS6.2-BL-EP")
      (description "DRV8870 具有电流调节功能的 50V、3.6A、H 桥电机驱动器")
      (fields (field (name "Manufacturer") "TI(德州仪器)"))
      (libsource (lib "easyedapro") (part "DRV8870DDAR"))
    )
    (comp (ref "U19")
      (value "RS0104YQ")
      (footprint "easyedapro:TSSOP-14_L5.0-W4.4-P0.65-LS6.4-BL")
      (description "数据速率:24Mbps;电压(VCCA):1.65V~5.5V;电压(VCCB):2.3V~5.5V;电路数:1;每个电路通道数:4;")
      (fields (field (name "Manufacturer") "RUNIC(润石)"))
      (libsource (lib "easyedapro") (part "RS0104YQ"))
    )
    (comp (ref "U20")
      (value "RS0104YQ")
      (footprint "easyedapro:TSSOP-14_L5.0-W4.4-P0.65-LS6.4-BL")
      (description "数据速率:24Mbps;电压(VCCA):1.65V~5.5V;电压(VCCB):2.3V~5.5V;电路数:1;每个电路通道数:4;")
      (fields (field (name "Manufacturer") "RUNIC(润石)"))
      (libsource (lib "easyedapro") (part "RS0104YQ"))
    )
    (comp (ref "U21")
      (value "RS0104YQ")
      (footprint "easyedapro:TSSOP-14_L5.0-W4.4-P0.65-LS6.4-BL")
      (description "数据速率:24Mbps;电压(VCCA):1.65V~5.5V;电压(VCCB):2.3V~5.5V;电路数:1;每个电路通道数:4;")
      (fields (field (name "Manufacturer") "RUNIC(润石)"))
      (libsource (lib "easyedapro") (part "RS0104YQ"))
    )
    (comp (ref "U22")
      (value "RS0104YQ")
      (footprint "easyedapro:TSSOP-14_L5.0-W4.4-P0.65-LS6.4-BL")
      (description "数据速率:24Mbps;电压(VCCA):1.65V~5.5V;电压(VCCB):2.3V~5.5V;电路数:1;每个电路通道数:4;")
      (fields (field (name "Manufacturer") "RUNIC(润石)"))
      (libsource (lib "easyedapro") (part "RS0104YQ"))
    )
    (comp (ref "U23")
      (value "DRV8825PWPR")
      (footprint "easyedapro:HTSSOP-28_L9.7-W4.4-P0.65-LS6.4-BL-EP")
      (description "DRV8825 具有电流调节功能和 1/32 微步进的 45V、2.5A 双极步进电机驱动器")
      (fields (field (name "Manufacturer") "TI(德州仪器)"))
      (libsource (lib "easyedapro") (part "DRV8825PWPR"))
    )
    (comp (ref "C105")
      (value "100nF")
      (footprint "easyedapro:C0603")
      (libsource (lib "easyedapro") (part "CapAcitance"))
    )
    (comp (ref "P1")
      (value "WJ500V-5.08-3P")
      (footprint "easyedapro:CONN-TH_3P-P5.00_WJ500V-5.08-3P")
      (fields (field (name "Manufacturer") "KANGNEX(康奈克斯电气)"))
      (libsource (lib "easyedapro") (part "WJ500V-5.08-3P-14-00A"))
    )
    (comp (ref "Q1")
      (value "SS8050")
      (footprint "easyedapro:SOT-23-3_L2.9-W1.3-P1.90-LS2.4-BR")
      (description "晶体管类型:NPN;集电极电流(Ic):1.5A;集射极击穿电压(Vceo):25V;耗散功率(Pd):300mW;直流电流增益(hFE):120@100mA,1.0V;")
      (fields (field (name "Manufacturer") "宏嘉诚"))
      (libsource (lib "easyedapro") (part "SS8050_C7420370"))
    )
    (comp (ref "R44") (value "10K") (footprint "easyedapro:R0603") (libsource (lib "easyedapro") (part "电阻")))
    (comp (ref "R45") (value "1K") (footprint "easyedapro:R0603") (libsource (lib "easyedapro") (part "电阻")))
    (comp (ref "U25")
      (value "W25Q16JVSNIQ")
      (footprint "easyedapro:SOP-8_L4.9-W3.9-P1.27-LS6.0-BL")
      (fields (field (name "Manufacturer") "WINBOND(华邦)"))
      (libsource (lib "easyedapro") (part "W25Q16JVSNIQ TR"))
    )
    (comp (ref "U26")
      (value "ZX-PM2.54-1-2PY")
      (footprint "easyedapro:HDR-TH_2P-P2.54-V-F")
      (fields (field (name "Manufacturer") "Megastar(兆星)"))
      (libsource (lib "easyedapro") (part "ZX-PM2.54-1-2PY"))
    )
  )
  (nets
    (net (code "1") (name "3V") (class "Default")
      (node (ref "B1") (pin "2") (pinfunction "2_2") (pintype "input"))
      (node (ref "C106") (pin "1") (pinfunction "1_1") (pintype "input"))
      (node (ref "R48") (pin "1") (pinfunction "1_1") (pintype "input"))
      (node (ref "U24") (pin "1") (pinfunction "1_1") (pintype "unspecified"))
    )
    (net (code "2") (name "3V3") (class "Default")
      (node (ref "C10") (pin "2") (pinfunction "2_2") (pintype "input"))
      (node (ref "C103") (pin "2") (pinfunction "2_2") (pintype "input"))
      (node (ref "C105") (pin "2") (pinfunction "2_2") (pintype "input"))
      (node (ref "C11") (pin "2") (pinfunction "2_2") (pintype "input"))
      (node (ref "C12") (pin "2") (pinfunction "2_2") (pintype "input"))
      (node (ref "C13") (pin "2") (pinfunction "2_2") (pintype "input"))
      (node (ref "C14") (pin "2") (pinfunction "2_2") (pintype "input"))
      (node (ref "C15") (pin "2") (pinfunction "2_2") (pintype "input"))
      (node (ref "C17") (pin "2") (pinfunction "2_2") (pintype "input"))
      (node (ref "C18") (pin "2") (pinfunction "2_2") (pintype "input"))
      (node (ref "C19") (pin "1") (pinfunction "1_1") (pintype "input"))
      (node (ref "C27") (pin "1") (pinfunction "1_1") (pintype "input"))
      (node (ref "C29") (pin "1") (pinfunction "1_1") (pintype "input"))
      (node (ref "C31") (pin "1") (pinfunction "1_1") (pintype "input"))
      (node (ref "C33") (pin "1") (pinfunction "1_1") (pintype "input"))
      (node (ref "C79") (pin "2") (pinfunction "2_2") (pintype "input"))
      (node (ref "C80") (pin "2") (pinfunction "2_2") (pintype "input"))
      (node (ref "C81") (pin "2") (pinfunction "2_2") (pintype "unspecified"))
      (node (ref "C91") (pin "1") (pinfunction "1_1") (pintype "input"))
      (node (ref "C93") (pin "1") (pinfunction "1_1") (pintype "input"))
      (node (ref "C95") (pin "1") (pinfunction "1_1") (pintype "input"))
      (node (ref "H1") (pin "2") (pinfunction "2_2") (pintype "unspecified"))
      (node (ref "L7") (pin "1") (pinfunction "1_1") (pintype "unspecified"))
      (node (ref "R2") (pin "1") (pinfunction "1_1") (pintype "input"))
      (node (ref "R31") (pin "2") (pinfunction "2_2") (pintype "input"))
      (node (ref "R4") (pin "2") (pinfunction "2_2") (pintype "input"))
      (node (ref "R44") (pin "2") (pinfunction "2_2") (pintype "input"))
      (node (ref "U1") (pin "100") (pinfunction "VDD_100") (pintype "unspecified"))
      (node (ref "U1") (pin "11") (pinfunction "VDD_11") (pintype "unspecified"))
      (node (ref "U1") (pin "19") (pinfunction "VDD_19") (pintype "unspecified"))
      (node (ref "U1") (pin "28") (pinfunction "VDD_28") (pintype "unspecified"))
      (node (ref "U1") (pin "50") (pinfunction "VDD_50") (pintype "unspecified"))
      (node (ref "U1") (pin "6") (pinfunction "VBAT_6") (pintype "unspecified"))
      (node (ref "U1") (pin "75") (pinfunction "VDD_75") (pintype "unspecified"))
      (node (ref "U19") (pin "1") (pinfunction "VCCA_1") (pintype "unspecified"))
      (node (ref "U19") (pin "8") (pinfunction "OE_8") (pintype "unspecified"))
      (node (ref "U20") (pin "1") (pinfunction "VCCA_1") (pintype "unspecified"))
      (node (ref "U20") (pin "8") (pinfunction "OE_8") (pintype "unspecified"))
      (node (ref "U21") (pin "1") (pinfunction "VCCA_1") (pintype "unspecified"))
      (node (ref "U21") (pin "8") (pinfunction "OE_8") (pintype "unspecified"))
      (node (ref "U22") (pin "1") (pinfunction "VCCA_1") (pintype "unspecified"))
      (node (ref "U22") (pin "8") (pinfunction "OE_8") (pintype "unspecified"))
      (node (ref "U25") (pin "3") (pinfunction "WP#/IO2_3") (pintype "unspecified"))
      (node (ref "U25") (pin "7") (pinfunction "HOLD#/RESET#/IO3_7") (pintype "unspecified"))
      (node (ref "U25") (pin "8") (pinfunction "VCC_8") (pintype "unspecified"))
      (node (ref "U6") (pin "1") (pinfunction "VCCA_1") (pintype "unspecified"))
      (node (ref "U7") (pin "1") (pinfunction "VCCA_1") (pintype "unspecified"))
      (node (ref "U8") (pin "1") (pinfunction "VCCA_1") (pintype "unspecified"))
      (node (ref "U9") (pin "1") (pinfunction "VCCA_1") (pintype "unspecified"))
    )
    (net (code "3") (name "5V") (class "Default")
      (node (ref "C20") (pin "1") (pinfunction "1_1") (pintype "input"))
      (node (ref "C28") (pin "1") (pinfunction "1_1") (pintype "input"))
      (node (ref "C30") (pin "1") (pinfunction "1_1") (pintype "input"))
      (node (ref "C32") (pin "1") (pinfunction "1_1") (pintype "input"))
      (node (ref "C34") (pin "1") (pinfunction "1_1") (pintype "input"))
      (node (ref "C85") (pin "2") (pinfunction "2_2") (pintype "input"))
      (node (ref "C86") (pin "2") (pinfunction "2_2") (pintype "input"))
      (node (ref "C87") (pin "2") (pinfunction "2_2") (pintype "unspecified"))
      (node (ref "C92") (pin "1") (pinfunction "1_1") (pintype "input"))
      (node (ref "C94") (pin "1") (pinfunction "1_1") (pintype "input"))
      (node (ref "C96") (pin "1") (pinfunction "1_1") (pintype "input"))
      (node (ref "L8") (pin "1") (pinfunction "1_1") (pintype "unspecified"))
      (node (ref "P1") (pin "2") (pinfunction "2_2") (pintype "unspecified"))
      (node (ref "R34") (pin "2") (pinfunction "2_2") (pintype "input"))
      (node (ref "U19") (pin "14") (pinfunction "VCCB_14") (pintype "unspecified"))
      (node (ref "U20") (pin "14") (pinfunction "VCCB_14") (pintype "unspecified"))
      (node (ref "U21") (pin "14") (pinfunction "VCCB_14") (pintype "unspecified"))
      (node (ref "U22") (pin "14") (pinfunction "VCCB_14") (pintype "unspecified"))
      (node (ref "U6") (pin "6") (pinfunction "VCCB_6") (pintype "unspecified"))
      (node (ref "U7") (pin "6") (pinfunction "VCCB_6") (pintype "unspecified"))
      (node (ref "U8") (pin "6") (pinfunction "VCCB_6") (pintype "unspecified"))
      (node (ref "U9") (pin "6") (pinfunction "VCCB_6") (pintype "unspecified"))
    )
    (net (code "4") (name "BLDC1_24V") (class "Default")
      (node (ref "C110") (pin "1") (pinfunction "1_1") (pintype "input"))
      (node (ref "C128") (pin "2") (pinfunction "2_2") (pintype "unspecified"))
      (node (ref "CN2") (pin "2") (pinfunction "2_2") (pintype "unspecified"))
      (node (ref "D1") (pin "2") (pinfunction "K_2") (pintype "unspecified"))
      (node (ref "R51") (pin "2") (pinfunction "2_2") (pintype "input"))
    )
    (net (code "5") (name "BLDC1_BRA") (class "Default")
      (node (ref "CN2") (pin "6") (pinfunction "6_6") (pintype "unspecified"))
      (node (ref "U19") (pin "13") (pinfunction "B1_13") (pintype "unspecified"))
    )
    (net (code "6") (name "BLDC1_BRA_3V3") (class "Default")
      (node (ref "U1") (pin "60") (pinfunction "PD13_60") (pintype "unspecified"))
      (node (ref "U19") (pin "2") (pinfunction "A1_2") (pintype "unspecified"))
    )
    (net (code "7") (name "BLDC1_FG") (class "Default")
      (node (ref "CN2") (pin "3") (pinfunction "3_3") (pintype "unspecified"))
      (node (ref "U6") (pin "4") (pinfunction "B_4") (pintype "unspecified"))
    )
    (net (code "8") (name "BLDC1_FG_3V3") (class "Default")
      (node (ref "U1") (pin "59") (pinfunction "PD12_59") (pintype "unspecified"))
      (node (ref "U6") (pin "3") (pinfunction "A_3") (pintype "unspecified"))
    )
    (net (code "9") (name "BLDC1_PWM") (class "Default")
      (node (ref "CN2") (pin "4") (pinfunction "4_4") (pintype "unspecified"))
      (node (ref "U19") (pin "10") (pinfunction "B4_10") (pintype "unspecified"))
    )
    (net (code "10") (name "BLDC1_PWM_3V3") (class "Default")
      (node (ref "U1") (pin "62") (pinfunction "PD15_62") (pintype "unspecified"))
      (node (ref "U19") (pin "5") (pinfunction "A4_5") (pintype "unspecified"))
    )
    (net (code "11") (name "BLDC1_REV") (class "Default")
      (node (ref "CN2") (pin "5") (pinfunction "5_5") (pintype "unspecified"))
      (node (ref "U19") (pin "12") (pinfunction "B2_12") (pintype "unspecified"))
    )
    (net (code "12") (name "BLDC1_REV_3V3") (class "Default")
      (node (ref "U1") (pin "61") (pinfunction "PD14_61") (pintype "unspecified"))
      (node (ref "U19") (pin "3") (pinfunction "A2_3") (pintype "unspecified"))
    )
    (net (code "13") (name "BLDC2_24V") (class "Default")
      (node (ref "C114") (pin "1") (pinfunction "1_1") (pintype "input"))
      (node (ref "C130") (pin "2") (pinfunction "2_2") (pintype "unspecified"))
      (node (ref "CN3") (pin "2") (pinfunction "2_2") (pintype "unspecified"))
      (node (ref "D2") (pin "2") (pinfunction "K_2") (pintype "unspecified"))
      (node (ref "R53") (pin "2") (pinfunction "2_2") (pintype "input"))
    )
    (net (code "14") (name "BLDC2_BRA") (class "Default")
      (node (ref "CN3") (pin "6") (pinfunction "6_6") (pintype "unspecified"))
      (node (ref "U20") (pin "13") (pinfunction "B1_13") (pintype "unspecified"))
    )
    (net (code "15") (name "BLDC2_BRA_3V3") (class "Default")
      (node (ref "U1") (pin "33") (pinfunction "PC4_33") (pintype "unspecified"))
      (node (ref "U20") (pin "2") (pinfunction "A1_2") (pintype "unspecified"))
    )
    (net (code "16") (name "BLDC2_FG") (class "Default")
      (node (ref "CN3") (pin "3") (pinfunction "3_3") (pintype "unspecified"))
      (node (ref "U7") (pin "4") (pinfunction "B_4") (pintype "unspecified"))
    )
    (net (code "17") (name "BLDC2_FG_3V3") (class "Default")
      (node (ref "U1") (pin "31") (pinfunction "PA6_31") (pintype "unspecified"))
      (node (ref "U7") (pin "3") (pinfunction "A_3") (pintype "unspecified"))
    )
    (net (code "18") (name "BLDC2_PWM") (class "Default")
      (node (ref "CN3") (pin "4") (pinfunction "4_4") (pintype "unspecified"))
      (node (ref "U20") (pin "10") (pinfunction "B4_10") (pintype "unspecified"))
    )
    (net (code "19") (name "BLDC2_PWM_3V3") (class "Default")
      (node (ref "U1") (pin "36") (pinfunction "PB1_36") (pintype "unspecified"))
      (node (ref "U20") (pin "5") (pinfunction "A4_5") (pintype "unspecified"))
    )
    (net (code "20") (name "BLDC2_REV") (class "Default")
      (node (ref "CN3") (pin "5") (pinfunction "5_5") (pintype "unspecified"))
      (node (ref "U20") (pin "12") (pinfunction "B2_12") (pintype "unspecified"))
    )
    (net (code "21") (name "BLDC2_REV_3V3") (class "Default")
      (node (ref "U1") (pin "34") (pinfunction "PC5_34") (pintype "unspecified"))
      (node (ref "U20") (pin "3") (pinfunction "A2_3") (pintype "unspecified"))
    )
    (net (code "22") (name "BLDC3_24V") (class "Default")
      (node (ref "C118") (pin "1") (pinfunction "1_1") (pintype "input"))
      (node (ref "C132") (pin "2") (pinfunction "2_2") (pintype "unspecified"))
      (node (ref "CN4") (pin "2") (pinfunction "2_2") (pintype "unspecified"))
      (node (ref "D3") (pin "2") (pinfunction "K_2") (pintype "unspecified"))
      (node (ref "R55") (pin "2") (pinfunction "2_2") (pintype "input"))
    )
    (net (code "23") (name "BLDC3_BRA") (class "Default")
      (node (ref "CN4") (pin "6") (pinfunction "6_6") (pintype "unspecified"))
      (node (ref "U21") (pin "13") (pinfunction "B1_13") (pintype "unspecified"))
    )
    (net (code "24") (name "BLDC3_BRA_3V3") (class "Default")
      (node (ref "U1") (pin "25") (pinfunction "PA2_25") (pintype "unspecified"))
      (node (ref "U21") (pin "2") (pinfunction "A1_2") (pintype "unspecified"))
    )
    (net (code "25") (name "BLDC3_FG") (class "Default")
      (node (ref "CN4") (pin "3") (pinfunction "3_3") (pintype "unspecified"))
      (node (ref "U8") (pin "4") (pinfunction "B_4") (pintype "unspecified"))
    )
    (net (code "26") (name "BLDC3_FG_3V3") (class "Default")
      (node (ref "U1") (pin "24") (pinfunction "PA1_24") (pintype "unspecified"))
      (node (ref "U8") (pin "3") (pinfunction "A_3") (pintype "unspecified"))
    )
    (net (code "27") (name "BLDC3_PWM") (class "Default")
      (node (ref "CN4") (pin "4") (pinfunction "4_4") (pintype "unspecified"))
      (node (ref "U21") (pin "10") (pinfunction "B4_10") (pintype "unspecified"))
    )
    (net (code "28") (name "BLDC3_PWM_3V3") (class "Default")
      (node (ref "U1") (pin "26") (pinfunction "PA3_26") (pintype "unspecified"))
      (node (ref "U21") (pin "5") (pinfunction "A4_5") (pintype "unspecified"))
    )
    (net (code "29") (name "BLDC3_REV") (class "Default")
      (node (ref "CN4") (pin "5") (pinfunction "5_5") (pintype "unspecified"))
      (node (ref "U21") (pin "12") (pinfunction "B2_12") (pintype "unspecified"))
    )
    (net (code "30") (name "BLDC3_REV_3V3") (class "Default")
      (node (ref "U1") (pin "29") (pinfunction "PA4_29") (pintype "unspecified"))
      (node (ref "U21") (pin "3") (pinfunction "A2_3") (pintype "unspecified"))
    )
    (net (code "31") (name "BLDC4_24V") (class "Default")
      (node (ref "C122") (pin "1") (pinfunction "1_1") (pintype "input"))
      (node (ref "C135") (pin "2") (pinfunction "2_2") (pintype "unspecified"))
      (node (ref "CN5") (pin "2") (pinfunction "2_2") (pintype "unspecified"))
      (node (ref "D4") (pin "2") (pinfunction "K_2") (pintype "unspecified"))
      (node (ref "R57") (pin "2") (pinfunction "2_2") (pintype "input"))
    )
    (net (code "32") (name "BLDC4_BRA") (class "Default")
      (node (ref "CN5") (pin "6") (pinfunction "6_6") (pintype "unspecified"))
      (node (ref "U22") (pin "13") (pinfunction "B1_13") (pintype "unspecified"))
    )
    (net (code "33") (name "BLDC4_BRA_3V3") (class "Default")
      (node (ref "U1") (pin "42") (pinfunction "PE11_42") (pintype "unspecified"))
      (node (ref "U22") (pin "2") (pinfunction "A1_2") (pintype "unspecified"))
    )
    (net (code "34") (name "BLDC4_FG") (class "Default")
      (node (ref "CN5") (pin "3") (pinfunction "3_3") (pintype "unspecified"))
      (node (ref "U9") (pin "4") (pinfunction "B_4") (pintype "unspecified"))
    )
    (net (code "35") (name "BLDC4_FG_3V3") (class "Default")
      (node (ref "U1") (pin "40") (pinfunction "PE9_40") (pintype "unspecified"))
      (node (ref "U9") (pin "3") (pinfunction "A_3") (pintype "unspecified"))
    )
    (net (code "36") (name "BLDC4_PWM") (class "Default")
      (node (ref "CN5") (pin "4") (pinfunction "4_4") (pintype "unspecified"))
      (node (ref "U22") (pin "10") (pinfunction "B4_10") (pintype "unspecified"))
    )
    (net (code "37") (name "BLDC4_PWM_3V3") (class "Default")
      (node (ref "U1") (pin "45") (pinfunction "PE14_45") (pintype "unspecified"))
      (node (ref "U22") (pin "5") (pinfunction "A4_5") (pintype "unspecified"))
    )
    (net (code "38") (name "BLDC4_REV") (class "Default")
      (node (ref "CN5") (pin "5") (pinfunction "5_5") (pintype "unspecified"))
      (node (ref "U22") (pin "12") (pinfunction "B2_12") (pintype "unspecified"))
    )
    (net (code "39") (name "BLDC4_REV_3V3") (class "Default")
      (node (ref "U1") (pin "43") (pinfunction "PE12_43") (pintype "unspecified"))
      (node (ref "U22") (pin "3") (pinfunction "A2_3") (pintype "unspecified"))
    )
    (net (code "40") (name "BOOT0") (class "Default")
      (node (ref "H1") (pin "1") (pinfunction "1_1") (pintype "unspecified"))
      (node (ref "R1") (pin "2") (pinfunction "2_2") (pintype "input"))
      (node (ref "U1") (pin "94") (pinfunction "BOOT0_94") (pintype "unspecified"))
    )
    (net (code "41") (name "GND") (class "Default")
      (node (ref "B1") (pin "1") (pinfunction "1_1") (pintype "input"))
      (node (ref "C1") (pin "1") (pinfunction "1_1") (pintype "input"))
      (node (ref "C10") (pin "1") (pinfunction "1_1") (pintype "input"))
      (node (ref "C100") (pin "1") (pinfunction "1_1") (pintype "unspecified"))
      (node (ref "C101") (pin "1") (pinfunction "1_1") (pintype "unspecified"))
      (node (ref "C102") (pin "2") (pinfunction "2_2") (pintype "input"))
      (node (ref "C103") (pin "1") (pinfunction "1_1") (pintype "input"))
      (node (ref "C104") (pin "1") (pinfunction "1_1") (pintype "input"))
      (node (ref "C105") (pin "1") (pinfunction "1_1") (pintype "input"))
      (node (ref "C106") (pin "2") (pinfunction "2_2") (pintype "input"))
      (node (ref "C107") (pin "1") (pinfunction "1_1") (pintype "input"))
      (node (ref "C108") (pin "1") (pinfunction "1_1") (pintype "input"))
      (node (ref "C11") (pin "1") (pinfunction "1_1") (pintype "input"))
      (node (ref "C110") (pin "2") (pinfunction "2_2") (pintype "input"))
      (node (ref "C112") (pin "1") (pinfunction "1_1") (pintype "input"))
      (node (ref "C114") (pin "2") (pinfunction "2_2") (pintype "input"))
      (node (ref "C116") (pin "1") (pinfunction "1_1") (pintype "input"))
      (node (ref "C118") (pin "2") (pinfunction "2_2") (pintype "input"))
      (node (ref "C12") (pin "1") (pinfunction "1_1") (pintype "input"))
      (node (ref "C120") (pin "1") (pinfunction "1_1") (pintype "input"))
      (node (ref "C122") (pin "2") (pinfunction "2_2") (pintype "input"))
      (node (ref "C124") (pin "1") (pinfunction "1_1") (pintype "input"))
      (node (ref "C126") (pin "2") (pinfunction "2_2") (pintype "input"))
      (node (ref "C128") (pin "1") (pinfunction "1_1") (pintype "unspecified"))
      (node (ref "C129") (pin "1") (pinfunction "1_1") (pintype "unspecified"))
      (node (ref "C13") (pin "1") (pinfunction "1_1") (pintype "input"))
      (node (ref "C130") (pin "1") (pinfunction "1_1") (pintype "unspecified"))
      (node (ref "C131") (pin "1") (pinfunction "1_1") (pintype "unspecified"))
      (node (ref "C132") (pin "1") (pinfunction "1_1") (pintype "unspecified"))
      (node (ref "C133") (pin "1") (pinfunction "1_1") (pintype "unspecified"))
      (node (ref "C134") (pin "1") (pinfunction "1_1") (pintype "unspecified"))
      (node (ref "C135") (pin "1") (pinfunction "1_1") (pintype "unspecified"))
      (node (ref "C136") (pin "1") (pinfunction "1_1") (pintype "unspecified"))
      (node (ref "C137") (pin "1") (pinfunction "1_1") (pintype "unspecified"))
      (node (ref "C14") (pin "1") (pinfunction "1_1") (pintype "input"))
      (node (ref "C15") (pin "1") (pinfunction "1_1") (pintype "input"))
      (node (ref "C17") (pin "1") (pinfunction "1_1") (pintype "input"))
      (node (ref "C18") (pin "1") (pinfunction "1_1") (pintype "input"))
      (node (ref "C19") (pin "2") (pinfunction "2_2") (pintype "input"))
      (node (ref "C2") (pin "1") (pinfunction "1_1") (pintype "input"))
      (node (ref "C20") (pin "2") (pinfunction "2_2") (pintype "input"))
      (node (ref "C27") (pin "2") (pinfunction "2_2") (pintype "input"))
      (node (ref "C28") (pin "2") (pinfunction "2_2") (pintype "input"))
      (node (ref "C29") (pin "2") (pinfunction "2_2") (pintype "input"))
      (node (ref "C3") (pin "1") (pinfunction "1_1") (pintype "input"))
      (node (ref "C30") (pin "2") (pinfunction "2_2") (pintype "input"))
      (node (ref "C31") (pin "2") (pinfunction "2_2") (pintype "input"))
      (node (ref "C32") (pin "2") (pinfunction "2_2") (pintype "input"))
      (node (ref "C33") (pin "2") (pinfunction "2_2") (pintype "input"))
      (node (ref "C34") (pin "2") (pinfunction "2_2") (pintype "input"))
      (node (ref "C36") (pin "1") (pinfunction "1_1") (pintype "input"))
      (node (ref "C37") (pin "1") (pinfunction "1_1") (pintype "input"))
      (node (ref "C38") (pin "1") (pinfunction "1_1") (pintype "input"))
      (node (ref "C39") (pin "1") (pinfunction "1_1") (pintype "input"))
      (node (ref "C4") (pin "1") (pinfunction "1_1") (pintype "input"))
      (node (ref "C5") (pin "1") (pinfunction "1_1") (pintype "input"))
      (node (ref "C6") (pin "1") (pinfunction "1_1") (pintype "input"))
      (node (ref "C7") (pin "1") (pinfunction "1_1") (pintype "input"))
      (node (ref "C77") (pin "1") (pinfunction "1_1") (pintype "input"))
      (node (ref "C78") (pin "1") (pinfunction "1_1") (pintype "input"))
      (node (ref "C79") (pin "1") (pinfunction "1_1") (pintype "input"))
      (node (ref "C8") (pin "2") (pinfunction "2_2") (pintype "input"))
      (node (ref "C80") (pin "1") (pinfunction "1_1") (pintype "input"))
      (node (ref "C83") (pin "1") (pinfunction "1_1") (pintype "input"))
      (node (ref "C84") (pin "1") (pinfunction "1_1") (pintype "input"))
      (node (ref "C85") (pin "1") (pinfunction "1_1") (pintype "input"))
      (node (ref "C86") (pin "1") (pinfunction "1_1") (pintype "input"))
      (node (ref "C88") (pin "2") (pinfunction "2_2") (pintype "input"))
      (node (ref "C89") (pin "1") (pinfunction "1_1") (pintype "unspecified"))
      (node (ref "C91") (pin "2") (pinfunction "2_2") (pintype "input"))
      (node (ref "C92") (pin "2") (pinfunction "2_2") (pintype "input"))
      (node (ref "C93") (pin "2") (pinfunction "2_2") (pintype "input"))
      (node (ref "C94") (pin "2") (pinfunction "2_2") (pintype "input"))
      (node (ref "C95") (pin "2") (pinfunction "2_2") (pintype "input"))
      (node (ref "C96") (pin "2") (pinfunction "2_2") (pintype "input"))
      (node (ref "C98") (pin "1") (pinfunction "1_1") (pintype "input"))
      (node (ref "CN1") (pin "1") (pinfunction "-_1") (pintype "unspecified"))
      (node (ref "CN2") (pin "1") (pinfunction "1_1") (pintype "unspecified"))
      (node (ref "CN3") (pin "1") (pinfunction "1_1") (pintype "unspecified"))
      (node (ref "CN4") (pin "1") (pinfunction "1_1") (pintype "unspecified"))
      (node (ref "CN5") (pin "1") (pinfunction "1_1") (pintype "unspecified"))
      (node (ref "H1") (pin "3") (pinfunction "3_3") (pintype "unspecified"))
      (node (ref "LED1") (pin "2") (pinfunction "-_2") (pintype "unspecified"))
      (node (ref "LED2") (pin "1") (pinfunction "K_1") (pintype "unspecified"))
      (node (ref "P1") (pin "1") (pinfunction "1_1") (pintype "unspecified"))
      (node (ref "Q1") (pin "2") (pinfunction "E_2") (pintype "input"))
      (node (ref "Q2") (pin "3") (pinfunction "S_3") (pintype "unspecified"))
      (node (ref "R1") (pin "1") (pinfunction "1_1") (pintype "input"))
      (node (ref "R30") (pin "1") (pinfunction "1_1") (pintype "input"))
      (node (ref "R33") (pin "2") (pinfunction "2_2") (pintype "unspecified"))
      (node (ref "R36") (pin "2") (pinfunction "2_2") (pintype "unspecified"))
      (node (ref "R37") (pin "1") (pinfunction "1_1") (pintype "input"))
      (node (ref "R38") (pin "2") (pinfunction "2_2") (pintype "unspecified"))
      (node (ref "R41") (pin "1") (pinfunction "1_1") (pintype "unspecified"))
      (node (ref "R42") (pin "1") (pinfunction "1_1") (pintype "unspecified"))
      (node (ref "R48") (pin "2") (pinfunction "2_2") (pintype "input"))
      (node (ref "R5") (pin "1") (pinfunction "1_1") (pintype "input"))
      (node (ref "R52") (pin "1") (pinfunction "1_1") (pintype "input"))
      (node (ref "R54") (pin "1") (pinfunction "1_1") (pintype "input"))
      (node (ref "R56") (pin "1") (pinfunction "1_1") (pintype "input"))
      (node (ref "R58") (pin "1") (pinfunction "1_1") (pintype "input"))
      (node (ref "R6") (pin "1") (pinfunction "1_1") (pintype "unspecified"))
      (node (ref "R60") (pin "1") (pinfunction "1_1") (pintype "input"))
      (node (ref "R9") (pin "2") (pinfunction "2_2") (pintype "unspecified"))
      (node (ref "SW1") (pin "1") (pinfunction "1_1") (pintype "unspecified"))
      (node (ref "U1") (pin "10") (pinfunction "VSS_10") (pintype "unspecified"))
      (node (ref "U1") (pin "20") (pinfunction "VSSA_20") (pintype "unspecified"))
      (node (ref "U1") (pin "27") (pinfunction "VSS_27") (pintype "unspecified"))
      (node (ref "U1") (pin "74") (pinfunction "VSS_74") (pintype "unspecified"))
      (node (ref "U1") (pin "99") (pinfunction "VSS_99") (pintype "unspecified"))
      (node (ref "U10") (pin "1") (pinfunction "GND_1") (pintype "unspecified"))
      (node (ref "U16") (pin "1") (pinfunction "GND_1") (pintype "unspecified"))
      (node (ref "U17") (pin "1") (pinfunction "GND_1") (pintype "unspecified"))
      (node (ref "U18") (pin "1") (pinfunction "GND_1") (pintype "unspecified"))
      (node (ref "U18") (pin "9") (pinfunction "PAD_9") (pintype "unspecified"))
      (node (ref "U19") (pin "7") (pinfunction "GND_7") (pintype "unspecified"))
      (node (ref "U20") (pin "7") (pinfunction "GND_7") (pintype "unspecified"))
      (node (ref "U21") (pin "7") (pinfunction "GND_7") (pintype "unspecified"))
      (node (ref "U22") (pin "7") (pinfunction "GND_7") (pintype "unspecified"))
      (node (ref "U23") (pin "14") (pinfunction "GND_14") (pintype "unspecified"))
      (node (ref "U23") (pin "28") (pinfunction "GND_28") (pintype "unspecified"))
      (node (ref "U23") (pin "29") (pinfunction "EP_29") (pintype "unspecified"))
      (node (ref "U24") (pin "3") (pinfunction "3_3") (pintype "unspecified"))
      (node (ref "U25") (pin "4") (pinfunction "GND_4") (pintype "unspecified"))
      (node (ref "U27") (pin "2") (pinfunction "GND_2") (pintype "unspecified"))
      (node (ref "U28") (pin "2") (pinfunction "GND_2") (pintype "unspecified"))
      (node (ref "U29") (pin "2") (pinfunction "GND_2") (pintype "unspecified"))
      (node (ref "U30") (pin "2") (pinfunction "GND_2") (pintype "unspecified"))
      (node (ref "U31") (pin "2") (pinfunction "GND_2") (pintype "unspecified"))
      (node (ref "U6") (pin "2") (pinfunction "GND_2") (pintype "unspecified"))
      (node (ref "U6") (pin "5") (pinfunction "DIR_5") (pintype "unspecified"))
      (node (ref "U7") (pin "2") (pinfunction "GND_2") (pintype "unspecified"))
      (node (ref "U7") (pin "5") (pinfunction "DIR_5") (pintype "unspecified"))
      (node (ref "U8") (pin "2") (pinfunction "GND_2") (pintype "unspecified"))
      (node (ref "U8") (pin "5") (pinfunction "DIR_5") (pintype "unspecified"))
      (node (ref "U9") (pin "2") (pinfunction "GND_2") (pintype "unspecified"))
      (node (ref "U9") (pin "5") (pinfunction "DIR_5") (pintype "unspecified"))
    )
    (net (code "42") (name "MC7RE_SBUS") (class "Default")
      (node (ref "P1") (pin "3") (pinfunction "3_3") (pintype "unspecified"))
      (node (ref "R45") (pin "2") (pinfunction "2_2") (pintype "input"))
    )
    (net (code "43") (name "Net-(CN1-+)") (class "Default")
      (node (ref "CN1") (pin "2") (pinfunction "+_2") (pintype "unspecified"))
      (node (ref "R49") (pin "2") (pinfunction "2_2") (pintype "unspecified"))
    )
    (net (code "44") (name "Net-(D1-A)") (class "Default")
      (node (ref "D1") (pin "1") (pinfunction "A_1") (pintype "unspecified"))
      (node (ref "L9") (pin "1") (pinfunction "1_1") (pintype "unspecified"))
      (node (ref "U27") (pin "1") (pinfunction "SW_1") (pintype "unspecified"))
    )
    (net (code "45") (name "Net-(D2-A)") (class "Default")
      (node (ref "D2") (pin "1") (pinfunction "A_1") (pintype "unspecified"))
      (node (ref "L10") (pin "1") (pinfunction "1_1") (pintype "unspecified"))
      (node (ref "U28") (pin "1") (pinfunction "SW_1") (pintype "unspecified"))
    )
    (net (code "46") (name "Net-(D3-A)") (class "Default")
      (node (ref "D3") (pin "1") (pinfunction "A_1") (pintype "unspecified"))
      (node (ref "L11") (pin "1") (pinfunction "1_1") (pintype "unspecified"))
      (node (ref "U29") (pin "1") (pinfunction "SW_1") (pintype "unspecified"))
    )
    (net (code "47") (name "Net-(D4-A)") (class "Default")
      (node (ref "D4") (pin "1") (pinfunction "A_1") (pintype "unspecified"))
      (node (ref "L12") (pin "1") (pinfunction "1_1") (pintype "unspecified"))
      (node (ref "U30") (pin "1") (pinfunction "SW_1") (pintype "unspecified"))
    )
    (net (code "48") (name "Net-(D5-A)") (class "Default")
      (node (ref "D5") (pin "1") (pinfunction "A_1") (pintype "unspecified"))
      (node (ref "L13") (pin "1") (pinfunction "1_1") (pintype "unspecified"))
      (node (ref "U31") (pin "1") (pinfunction "SW_1") (pintype "unspecified"))
    )
    (net (code "49") (name "Net-(LED1-+)") (class "Default")
      (node (ref "LED1") (pin "1") (pinfunction "+_1") (pintype "unspecified"))
      (node (ref "R4") (pin "1") (pinfunction "1_1") (pintype "input"))
    )
    (net (code "50") (name "Net-(LED2-A)") (class "Default")
      (node (ref "LED2") (pin "2") (pinfunction "A_2") (pintype "unspecified"))
      (node (ref "R50") (pin "1") (pinfunction "1_1") (pintype "input"))
    )
    (net (code "51") (name "Net-(Q1-B)") (class "Default")
      (node (ref "Q1") (pin "1") (pinfunction "B_1") (pintype "input"))
      (node (ref "R45") (pin "1") (pinfunction "1_1") (pintype "input"))
    )
    (net (code "52") (name "Net-(Q2-G)") (class "Default")
      (node (ref "Q2") (pin "1") (pinfunction "G_1") (pintype "unspecified"))
      (node (ref "U24") (pin "2") (pinfunction "2_2") (pintype "unspecified"))
    )
    (net (code "53") (name "Net-(U1-NRST)") (class "Default")
      (node (ref "C1") (pin "2") (pinfunction "2_2") (pintype "input"))
      (node (ref "SW1") (pin "2") (pinfunction "2_2") (pintype "unspecified"))
      (node (ref "U1") (pin "14") (pinfunction "NRST_14") (pintype "unspecified"))
    )
    (net (code "54") (name "Net-(U1-PB2)") (class "Default")
      (node (ref "R5") (pin "2") (pinfunction "2_2") (pintype "input"))
      (node (ref "U1") (pin "37") (pinfunction "PB2_37") (pintype "unspecified"))
    )
    (net (code "55") (name "Net-(U1-PC14)") (class "Default")
      (node (ref "C6") (pin "2") (pinfunction "2_2") (pintype "input"))
      (node (ref "U1") (pin "8") (pinfunction "PC14_8") (pintype "unspecified"))
      (node (ref "X2") (pin "2") (pinfunction "2_2") (pintype "unspecified"))
    )
    (net (code "56") (name "Net-(U1-PC15)") (class "Default")
      (node (ref "C7") (pin "2") (pinfunction "2_2") (pintype "input"))
      (node (ref "U1") (pin "9") (pinfunction "PC15_9") (pintype "unspecified"))
      (node (ref "X2") (pin "1") (pinfunction "1_1") (pintype "unspecified"))
    )
    (net (code "57") (name "Net-(U1-PH0)") (class "Default")
      (node (ref "C5") (pin "2") (pinfunction "2_2") (pintype "input"))
      (node (ref "U1") (pin "12") (pinfunction "PH0_12") (pintype "unspecified"))
      (node (ref "X1") (pin "1") (pinfunction "OSC1_1") (pintype "input"))
    )
    (net (code "58") (name "Net-(U1-PH1)") (class "Default")
      (node (ref "C4") (pin "2") (pinfunction "2_2") (pintype "input"))
      (node (ref "U1") (pin "13") (pinfunction "PH1_13") (pintype "unspecified"))
      (node (ref "X1") (pin "2") (pinfunction "OSC2_2") (pintype "input"))
    )
    (net (code "59") (name "Net-(U1-VCAP_1)") (class "Default")
      (node (ref "C2") (pin "2") (pinfunction "2_2") (pintype "input"))
      (node (ref "U1") (pin "49") (pinfunction "VCAP_1_49") (pintype "unspecified"))
    )
    (net (code "60") (name "Net-(U1-VCAP_2)") (class "Default")
      (node (ref "C3") (pin "2") (pinfunction "2_2") (pintype "input"))
      (node (ref "U1") (pin "73") (pinfunction "VCAP_2_73") (pintype "unspecified"))
    )
    (net (code "61") (name "Net-(U1-VREF+)") (class "Default")
      (node (ref "R3") (pin "1") (pinfunction "1_1") (pintype "input"))
      (node (ref "U1") (pin "21") (pinfunction "VREF+_21") (pintype "unspecified"))
    )
    (net (code "62") (name "Net-(U10-BOOT)") (class "Default")
      (node (ref "C35") (pin "2") (pinfunction "2_2") (pintype "input"))
      (node (ref "U10") (pin "6") (pinfunction "BOOT_6") (pintype "unspecified"))
    )
    (net (code "63") (name "Net-(U10-EN)") (class "Default")
      (node (ref "R8") (pin "2") (pinfunction "2_2") (pintype "unspecified"))
      (node (ref "R9") (pin "1") (pinfunction "1_1") (pintype "unspecified"))
      (node (ref "U10") (pin "5") (pinfunction "EN_5") (pintype "unspecified"))
    )
    (net (code "64") (name "Net-(U10-SW)") (class "Default")
      (node (ref "C35") (pin "1") (pinfunction "1_1") (pintype "input"))
      (node (ref "L1") (pin "2") (pinfunction "2_2") (pintype "unspecified"))
      (node (ref "U10") (pin "2") (pinfunction "SW_2") (pintype "unspecified"))
    )
    (net (code "65") (name "Net-(U16-BOOT)") (class "Default")
      (node (ref "C76") (pin "2") (pinfunction "2_2") (pintype "input"))
      (node (ref "U16") (pin "6") (pinfunction "BOOT_6") (pintype "unspecified"))
    )
    (net (code "66") (name "Net-(U16-EN)") (class "Default")
      (node (ref "R32") (pin "2") (pinfunction "2_2") (pintype "unspecified"))
      (node (ref "R33") (pin "1") (pinfunction "1_1") (pintype "unspecified"))
      (node (ref "U16") (pin "5") (pinfunction "EN_5") (pintype "unspecified"))
    )
    (net (code "67") (name "Net-(U16-SW)") (class "Default")
      (node (ref "C76") (pin "1") (pinfunction "1_1") (pintype "input"))
      (node (ref "L7") (pin "2") (pinfunction "2_2") (pintype "unspecified"))
      (node (ref "U16") (pin "2") (pinfunction "SW_2") (pintype "unspecified"))
    )
    (net (code "68") (name "Net-(U17-BOOT)") (class "Default")
      (node (ref "C82") (pin "2") (pinfunction "2_2") (pintype "input"))
      (node (ref "U17") (pin "6") (pinfunction "BOOT_6") (pintype "unspecified"))
    )
    (net (code "69") (name "Net-(U17-EN)") (class "Default")
      (node (ref "R35") (pin "2") (pinfunction "2_2") (pintype "unspecified"))
      (node (ref "R36") (pin "1") (pinfunction "1_1") (pintype "unspecified"))
      (node (ref "U17") (pin "5") (pinfunction "EN_5") (pintype "unspecified"))
    )
    (net (code "70") (name "Net-(U17-SW)") (class "Default")
      (node (ref "C82") (pin "1") (pinfunction "1_1") (pintype "input"))
      (node (ref "L8") (pin "2") (pinfunction "2_2") (pintype "unspecified"))
      (node (ref "U17") (pin "2") (pinfunction "SW_2") (pintype "unspecified"))
    )
    (net (code "71") (name "Net-(U18-ISEN)") (class "Default")
      (node (ref "R38") (pin "1") (pinfunction "1_1") (pintype "unspecified"))
      (node (ref "U18") (pin "7") (pinfunction "ISEN_7") (pintype "unspecified"))
    )
    (net (code "72") (name "Net-(U23-CP1)") (class "Default")
      (node (ref "C97") (pin "2") (pinfunction "2_2") (pintype "input"))
      (node (ref "U23") (pin "1") (pinfunction "CP1_1") (pintype "unspecified"))
    )
    (net (code "73") (name "Net-(U23-CP2)") (class "Default")
      (node (ref "C97") (pin "1") (pinfunction "1_1") (pintype "input"))
      (node (ref "U23") (pin "2") (pinfunction "CP2_2") (pintype "unspecified"))
    )
    (net (code "74") (name "Net-(U23-ISENA)") (class "Default")
      (node (ref "R41") (pin "2") (pinfunction "2_2") (pintype "unspecified"))
      (node (ref "U23") (pin "6") (pinfunction "ISENA_6") (pintype "unspecified"))
    )
    (net (code "75") (name "Net-(U23-ISENB)") (class "Default")
      (node (ref "R42") (pin "2") (pinfunction "2_2") (pintype "unspecified"))
      (node (ref "U23") (pin "9") (pinfunction "ISENB_9") (pintype "unspecified"))
    )
    (net (code "76") (name "Net-(U23-VCP)") (class "Default")
      (node (ref "C99") (pin "2") (pinfunction "2_2") (pintype "unspecified"))
      (node (ref "R43") (pin "2") (pinfunction "2_2") (pintype "input"))
      (node (ref "U23") (pin "3") (pinfunction "VCP_3") (pintype "unspecified"))
    )
    (net (code "77") (name "Net-(U27-FB)") (class "Default")
      (node (ref "R51") (pin "1") (pinfunction "1_1") (pintype "input"))
      (node (ref "R52") (pin "2") (pinfunction "2_2") (pintype "input"))
      (node (ref "U27") (pin "3") (pinfunction "FB_3") (pintype "unspecified"))
    )
    (net (code "78") (name "Net-(U28-FB)") (class "Default")
      (node (ref "R53") (pin "1") (pinfunction "1_1") (pintype "input"))
      (node (ref "R54") (pin "2") (pinfunction "2_2") (pintype "input"))
      (node (ref "U28") (pin "3") (pinfunction "FB_3") (pintype "unspecified"))
    )
    (net (code "79") (name "Net-(U29-FB)") (class "Default")
      (node (ref "R55") (pin "1") (pinfunction "1_1") (pintype "input"))
      (node (ref "R56") (pin "2") (pinfunction "2_2") (pintype "input"))
      (node (ref "U29") (pin "3") (pinfunction "FB_3") (pintype "unspecified"))
    )
    (net (code "80") (name "Net-(U30-FB)") (class "Default")
      (node (ref "R57") (pin "1") (pinfunction "1_1") (pintype "input"))
      (node (ref "R58") (pin "2") (pinfunction "2_2") (pintype "input"))
      (node (ref "U30") (pin "3") (pinfunction "FB_3") (pintype "unspecified"))
    )
    (net (code "81") (name "Net-(U31-FB)") (class "Default")
      (node (ref "R59") (pin "1") (pinfunction "1_1") (pintype "input"))
      (node (ref "R60") (pin "2") (pinfunction "2_2") (pintype "input"))
      (node (ref "U31") (pin "3") (pinfunction "FB_3") (pintype "unspecified"))
    )
    (net (code "82") (name "ORI_24V") (class "Default")
      (node (ref "C107") (pin "2") (pinfunction "2_2") (pintype "input"))
      (node (ref "C108") (pin "2") (pinfunction "2_2") (pintype "input"))
      (node (ref "C112") (pin "2") (pinfunction "2_2") (pintype "input"))
      (node (ref "C116") (pin "2") (pinfunction "2_2") (pintype "input"))
      (node (ref "C120") (pin "2") (pinfunction "2_2") (pintype "input"))
      (node (ref "C124") (pin "2") (pinfunction "2_2") (pintype "input"))
      (node (ref "C129") (pin "2") (pinfunction "2_2") (pintype "unspecified"))
      (node (ref "C131") (pin "2") (pinfunction "2_2") (pintype "unspecified"))
      (node (ref "C133") (pin "2") (pinfunction "2_2") (pintype "unspecified"))
      (node (ref "C134") (pin "2") (pinfunction "2_2") (pintype "unspecified"))
      (node (ref "C137") (pin "2") (pinfunction "2_2") (pintype "unspecified"))
      (node (ref "C36") (pin "2") (pinfunction "2_2") (pintype "input"))
      (node (ref "C37") (pin "2") (pinfunction "2_2") (pintype "input"))
      (node (ref "C77") (pin "2") (pinfunction "2_2") (pintype "input"))
      (node (ref "C78") (pin "2") (pinfunction "2_2") (pintype "input"))
      (node (ref "C83") (pin "2") (pinfunction "2_2") (pintype "input"))
      (node (ref "C84") (pin "2") (pinfunction "2_2") (pintype "input"))
      (node (ref "L10") (pin "2") (pinfunction "2_2") (pintype "unspecified"))
      (node (ref "L11") (pin "2") (pinfunction "2_2") (pintype "unspecified"))
      (node (ref "L12") (pin "2") (pinfunction "2_2") (pintype "unspecified"))
      (node (ref "L13") (pin "2") (pinfunction "2_2") (pintype "unspecified"))
      (node (ref "L9") (pin "2") (pinfunction "2_2") (pintype "unspecified"))
      (node (ref "Q2") (pin "2") (pinfunction "D_2") (pintype "unspecified"))
      (node (ref "R32") (pin "1") (pinfunction "1_1") (pintype "unspecified"))
      (node (ref "R35") (pin "1") (pinfunction "1_1") (pintype "unspecified"))
      (node (ref "R49") (pin "1") (pinfunction "1_1") (pintype "unspecified"))
      (node (ref "R50") (pin "2") (pinfunction "2_2") (pintype "input"))
      (node (ref "R8") (pin "1") (pinfunction "1_1") (pintype "unspecified"))
      (node (ref "U10") (pin "3") (pinfunction "VIN_3") (pintype "unspecified"))
      (node (ref "U16") (pin "3") (pinfunction "VIN_3") (pintype "unspecified"))
      (node (ref "U17") (pin "3") (pinfunction "VIN_3") (pintype "unspecified"))
      (node (ref "U27") (pin "4") (pinfunction "EN_4") (pintype "unspecified"))
      (node (ref "U27") (pin "5") (pinfunction "IN_5") (pintype "unspecified"))
      (node (ref "U28") (pin "4") (pinfunction "EN_4") (pintype "unspecified"))
      (node (ref "U28") (pin "5") (pinfunction "IN_5") (pintype "unspecified"))
      (node (ref "U29") (pin "4") (pinfunction "EN_4") (pintype "unspecified"))
      (node (ref "U29") (pin "5") (pinfunction "IN_5") (pintype "unspecified"))
      (node (ref "U30") (pin "4") (pinfunction "EN_4") (pintype "unspecified"))
      (node (ref "U30") (pin "5") (pinfunction "IN_5") (pintype "unspecified"))
      (node (ref "U31") (pin "4") (pinfunction "EN_4") (pintype "unspecified"))
      (node (ref "U31") (pin "5") (pinfunction "IN_5") (pintype "unspecified"))
    )
    (net (code "83") (name "PUMP_12V") (class "Default")
      (node (ref "C38") (pin "2") (pinfunction "2_2") (pintype "input"))
      (node (ref "C39") (pin "2") (pinfunction "2_2") (pintype "input"))
      (node (ref "C40") (pin "2") (pinfunction "2_2") (pintype "unspecified"))
      (node (ref "C88") (pin "1") (pinfunction "1_1") (pintype "input"))
      (node (ref "C89") (pin "2") (pinfunction "2_2") (pintype "unspecified"))
      (node (ref "L1") (pin "1") (pinfunction "1_1") (pintype "unspecified"))
      (node (ref "R7") (pin "2") (pinfunction "2_2") (pintype "input"))
      (node (ref "U18") (pin "5") (pinfunction "VM_5") (pintype "unspecified"))
    )
    (net (code "84") (name "PUMP_IN1") (class "Default")
      (node (ref "U1") (pin "96") (pinfunction "PB9_96") (pintype "unspecified"))
      (node (ref "U18") (pin "3") (pinfunction "IN1_3") (pintype "unspecified"))
    )
    (net (code "85") (name "PUMP_IN2") (class "Default")
      (node (ref "U1") (pin "95") (pinfunction "PB8_95") (pintype "unspecified"))
      (node (ref "U18") (pin "2") (pinfunction "IN2_2") (pintype "unspecified"))
    )
    (net (code "86") (name "PUMP_OUT1") (class "Default")
      (node (ref "C90") (pin "1") (pinfunction "1_1") (pintype "unspecified"))
      (node (ref "DC1") (pin "1") (pinfunction "1_1") (pintype "unspecified"))
      (node (ref "U18") (pin "6") (pinfunction "OUT1_6") (pintype "unspecified"))
    )
    (net (code "87") (name "PUMP_OUT2") (class "Default")
      (node (ref "C90") (pin "2") (pinfunction "2_2") (pintype "unspecified"))
      (node (ref "DC1") (pin "2") (pinfunction "2_2") (pintype "unspecified"))
      (node (ref "U18") (pin "8") (pinfunction "OUT2_8") (pintype "unspecified"))
    )
    (net (code "88") (name "PUMP_VREF") (class "Default")
      (node (ref "U1") (pin "97") (pinfunction "PE0_97") (pintype "unspecified"))
      (node (ref "U18") (pin "4") (pinfunction "VREF_4") (pintype "unspecified"))
    )
    (net (code "89") (name "REMOTE_DATA") (class "Default")
      (node (ref "Q1") (pin "3") (pinfunction "C_3") (pintype "input"))
      (node (ref "R44") (pin "1") (pinfunction "1_1") (pintype "input"))
      (node (ref "U1") (pin "87") (pinfunction "PD6_87") (pintype "unspecified"))
    )
    (net (code "90") (name "SPI3_CS") (class "Default")
      (node (ref "U1") (pin "77") (pinfunction "PA15_77") (pintype "unspecified"))
      (node (ref "U25") (pin "1") (pinfunction "CS#_1") (pintype "unspecified"))
    )
    (net (code "91") (name "SPI3_MISO") (class "Default")
      (node (ref "U1") (pin "79") (pinfunction "PC11_79") (pintype "unspecified"))
      (node (ref "U25") (pin "2") (pinfunction "DO/IO1_2") (pintype "unspecified"))
    )
    (net (code "92") (name "SPI3_MOSI") (class "Default")
      (node (ref "U1") (pin "80") (pinfunction "PC12_80") (pintype "unspecified"))
      (node (ref "U25") (pin "5") (pinfunction "DI/IO0_5") (pintype "unspecified"))
    )
    (net (code "93") (name "SPI3_SCK") (class "Default")
      (node (ref "U1") (pin "78") (pinfunction "PC10_78") (pintype "unspecified"))
      (node (ref "U25") (pin "6") (pinfunction "CLK_6") (pintype "unspecified"))
    )
    (net (code "94") (name "STEPPER_24V") (class "Default")
      (node (ref "C100") (pin "2") (pinfunction "2_2") (pintype "unspecified"))
      (node (ref "C101") (pin "2") (pinfunction "2_2") (pintype "unspecified"))
      (node (ref "C102") (pin "1") (pinfunction "1_1") (pintype "input"))
      (node (ref "C126") (pin "1") (pinfunction "1_1") (pintype "input"))
      (node (ref "C136") (pin "2") (pinfunction "2_2") (pintype "unspecified"))
      (node (ref "C99") (pin "1") (pinfunction "1_1") (pintype "unspecified"))
      (node (ref "D5") (pin "2") (pinfunction "K_2") (pintype "unspecified"))
      (node (ref "R43") (pin "1") (pinfunction "1_1") (pintype "input"))
      (node (ref "R59") (pin "2") (pinfunction "2_2") (pintype "input"))
      (node (ref "U23") (pin "11") (pinfunction "VMB_11") (pintype "unspecified"))
      (node (ref "U23") (pin "4") (pinfunction "VMA_4") (pintype "unspecified"))
    )
    (net (code "95") (name "STEPPER_AOUT1") (class "Default")
      (node (ref "CN6") (pin "1") (pinfunction "1_1") (pintype "unspecified"))
      (node (ref "U23") (pin "5") (pinfunction "AOUT1_5") (pintype "unspecified"))
    )
    (net (code "96") (name "STEPPER_AOUT2") (class "Default")
      (node (ref "CN6") (pin "2") (pinfunction "2_2") (pintype "unspecified"))
      (node (ref "U23") (pin "7") (pinfunction "AOUT2_7") (pintype "unspecified"))
    )
    (net (code "97") (name "STEPPER_BOUT1") (class "Default")
      (node (ref "CN6") (pin "4") (pinfunction "4_4") (pintype "unspecified"))
      (node (ref "U23") (pin "10") (pinfunction "BOUT1_10") (pintype "unspecified"))
    )
    (net (code "98") (name "STEPPER_BOUT2") (class "Default")
      (node (ref "CN6") (pin "3") (pinfunction "3_3") (pintype "unspecified"))
      (node (ref "U23") (pin "8") (pinfunction "BOUT2_8") (pintype "unspecified"))
    )
    (net (code "99") (name "STEPPER_DECAY") (class "Default")
      (node (ref "U1") (pin "57") (pinfunction "PD10_57") (pintype "unspecified"))
      (node (ref "U23") (pin "19") (pinfunction "DECAY_19") (pintype "unspecified"))
    )
    (net (code "100") (name "STEPPER_DIR") (class "Default")
      (node (ref "U1") (pin "56") (pinfunction "PD9_56") (pintype "unspecified"))
      (node (ref "U23") (pin "20") (pinfunction "DIR_20") (pintype "unspecified"))
    )
    (net (code "101") (name "STEPPER_MODE0") (class "Default")
      (node (ref "U1") (pin "53") (pinfunction "PB14_53") (pintype "unspecified"))
      (node (ref "U23") (pin "24") (pinfunction "MODE0_24") (pintype "unspecified"))
    )
    (net (code "102") (name "STEPPER_MODE1") (class "Default")
      (node (ref "U1") (pin "52") (pinfunction "PB13_52") (pintype "unspecified"))
      (node (ref "U23") (pin "25") (pinfunction "MODE1_25") (pintype "unspecified"))
    )
    (net (code "103") (name "STEPPER_MODE2") (class "Default")
      (node (ref "U1") (pin "51") (pinfunction "PB12_51") (pintype "unspecified"))
      (node (ref "U23") (pin "26") (pinfunction "MODE2_26") (pintype "unspecified"))
    )
    (net (code "104") (name "STEPPER_NEABL") (class "Default")
      (node (ref "U1") (pin "55") (pinfunction "PD8_55") (pintype "unspecified"))
      (node (ref "U23") (pin "21") (pinfunction "NENBL_21") (pintype "unspecified"))
    )
    (net (code "105") (name "STEPPER_NFLT") (class "Default")
      (node (ref "R40") (pin "1") (pinfunction "1_1") (pintype "input"))
      (node (ref "U1") (pin "64") (pinfunction "PC7_64") (pintype "unspecified"))
      (node (ref "U23") (pin "18") (pinfunction "nFAULT_18") (pintype "unspecified"))
    )
    (net (code "106") (name "STEPPER_NHOME") (class "Default")
      (node (ref "R39") (pin "1") (pinfunction "1_1") (pintype "input"))
      (node (ref "U1") (pin "58") (pinfunction "PD11_58") (pintype "unspecified"))
      (node (ref "U23") (pin "27") (pinfunction "nHOME_27") (pintype "unspecified"))
    )
    (net (code "107") (name "STEPPER_NRST") (class "Default")
      (node (ref "U1") (pin "65") (pinfunction "PC8_65") (pintype "unspecified"))
      (node (ref "U23") (pin "16") (pinfunction "nRESET_16") (pintype "unspecified"))
    )
    (net (code "108") (name "STEPPER_NSLP") (class "Default")
      (node (ref "U1") (pin "63") (pinfunction "PC6_63") (pintype "unspecified"))
      (node (ref "U23") (pin "17") (pinfunction "nSLEEP_17") (pintype "unspecified"))
    )
    (net (code "109") (name "STEPPER_STEP") (class "Default")
      (node (ref "U1") (pin "54") (pinfunction "PB15_54") (pintype "unspecified"))
      (node (ref "U23") (pin "22") (pinfunction "STEP_22") (pintype "unspecified"))
    )
    (net (code "110") (name "STEPPER_V3P3OUT") (class "Default")
      (node (ref "C98") (pin "2") (pinfunction "2_2") (pintype "input"))
      (node (ref "R39") (pin "2") (pinfunction "2_2") (pintype "input"))
      (node (ref "R40") (pin "2") (pinfunction "2_2") (pintype "input"))
      (node (ref "U23") (pin "12") (pinfunction "AVREF_12") (pintype "unspecified"))
      (node (ref "U23") (pin "13") (pinfunction "BVREF_13") (pintype "unspecified"))
      (node (ref "U23") (pin "15") (pinfunction "V3P3OUT_15") (pintype "unspecified"))
    )
    (net (code "111") (name "SWCLK") (class "Default")
      (node (ref "H1") (pin "5") (pinfunction "5_5") (pintype "unspecified"))
      (node (ref "U1") (pin "76") (pinfunction "PA14_76") (pintype "unspecified"))
    )
    (net (code "112") (name "SWDIO") (class "Default")
      (node (ref "H1") (pin "4") (pinfunction "4_4") (pintype "unspecified"))
      (node (ref "U1") (pin "72") (pinfunction "PA13_72") (pintype "unspecified"))
    )
    (net (code "113") (name "U10_FB") (class "Default")
      (node (ref "C40") (pin "1") (pinfunction "1_1") (pintype "unspecified"))
      (node (ref "R6") (pin "2") (pinfunction "2_2") (pintype "unspecified"))
      (node (ref "R7") (pin "1") (pinfunction "1_1") (pintype "input"))
      (node (ref "U10") (pin "4") (pinfunction "FB_4") (pintype "unspecified"))
    )
    (net (code "114") (name "U16_FB") (class "Default")
      (node (ref "C81") (pin "1") (pinfunction "1_1") (pintype "unspecified"))
      (node (ref "R30") (pin "2") (pinfunction "2_2") (pintype "input"))
      (node (ref "R31") (pin "1") (pinfunction "1_1") (pintype "input"))
      (node (ref "U16") (pin "4") (pinfunction "FB_4") (pintype "unspecified"))
    )
    (net (code "115") (name "U17_FB") (class "Default")
      (node (ref "C87") (pin "1") (pinfunction "1_1") (pintype "unspecified"))
      (node (ref "R34") (pin "1") (pinfunction "1_1") (pintype "input"))
      (node (ref "R37") (pin "2") (pinfunction "2_2") (pintype "input"))
      (node (ref "U17") (pin "4") (pinfunction "FB_4") (pintype "unspecified"))
    )
    (net (code "116") (name "USART1_RX") (class "Default")
      (node (ref "U1") (pin "69") (pinfunction "PA10_69") (pintype "unspecified"))
      (node (ref "U26") (pin "2") (pinfunction "2_2") (pintype "unspecified"))
    )
    (net (code "117") (name "USART1_TX") (class "Default")
      (node (ref "U1") (pin "68") (pinfunction "PA9_68") (pintype "unspecified"))
      (node (ref "U26") (pin "1") (pinfunction "1_1") (pintype "unspecified"))
    )
    (net (code "118") (name "VDDA") (class "Default")
      (node (ref "C104") (pin "2") (pinfunction "2_2") (pintype "input"))
      (node (ref "C8") (pin "1") (pinfunction "1_1") (pintype "input"))
      (node (ref "R2") (pin "2") (pinfunction "2_2") (pintype "input"))
      (node (ref "R3") (pin "2") (pinfunction "2_2") (pintype "input"))
      (node (ref "U1") (pin "22") (pinfunction "VDDA_22") (pintype "unspecified"))
    )
    (net (code "119") (name "unconnected-(CN1-Pad3)") (class "Default")
      (node (ref "CN1") (pin "3") (pinfunction "3_3") (pintype "unspecified+no_connect"))
    )
    (net (code "120") (name "unconnected-(CN1-Pad4)") (class "Default")
      (node (ref "CN1") (pin "4") (pinfunction "4_4") (pintype "unspecified+no_connect"))
    )
    (net (code "121") (name "unconnected-(DC1-Pad3)") (class "Default")
      (node (ref "DC1") (pin "3") (pinfunction "3_3") (pintype "unspecified+no_connect"))
    )
    (net (code "122") (name "unconnected-(U1-PA0-Pad23)") (class "Default")
      (node (ref "U1") (pin "23") (pinfunction "PA0_23") (pintype "unspecified"))
    )
    (net (code "123") (name "unconnected-(U1-PA5-Pad30)") (class "Default")
      (node (ref "U1") (pin "30") (pinfunction "PA5_30") (pintype "unspecified"))
    )
    (net (code "124") (name "unconnected-(U1-PA7-Pad32)") (class "Default")
      (node (ref "U1") (pin "32") (pinfunction "PA7_32") (pintype "unspecified"))
    )
    (net (code "125") (name "unconnected-(U1-PA8-Pad67)") (class "Default")
      (node (ref "U1") (pin "67") (pinfunction "PA8_67") (pintype "unspecified"))
    )
    (net (code "126") (name "unconnected-(U1-PA11-Pad70)") (class "Default")
      (node (ref "U1") (pin "70") (pinfunction "PA11_70") (pintype "unspecified"))
    )
    (net (code "127") (name "unconnected-(U1-PA12-Pad71)") (class "Default")
      (node (ref "U1") (pin "71") (pinfunction "PA12_71") (pintype "unspecified"))
    )
    (net (code "128") (name "unconnected-(U1-PB0-Pad35)") (class "Default")
      (node (ref "U1") (pin "35") (pinfunction "PB0_35") (pintype "unspecified"))
    )
    (net (code "129") (name "unconnected-(U1-PB3-Pad89)") (class "Default")
      (node (ref "U1") (pin "89") (pinfunction "PB3_89") (pintype "unspecified"))
    )
    (net (code "130") (name "unconnected-(U1-PB4-Pad90)") (class "Default")
      (node (ref "U1") (pin "90") (pinfunction "PB4_90") (pintype "unspecified"))
    )
    (net (code "131") (name "unconnected-(U1-PB5-Pad91)") (class "Default")
      (node (ref "U1") (pin "91") (pinfunction "PB5_91") (pintype "unspecified"))
    )
    (net (code "132") (name "unconnected-(U1-PB6-Pad92)") (class "Default")
      (node (ref "U1") (pin "92") (pinfunction "PB6_92") (pintype "unspecified"))
    )
    (net (code "133") (name "unconnected-(U1-PB7-Pad93)") (class "Default")
      (node (ref "U1") (pin "93") (pinfunction "PB7_93") (pintype "unspecified"))
    )
    (net (code "134") (name "unconnected-(U1-PB10-Pad47)") (class "Default")
      (node (ref "U1") (pin "47") (pinfunction "PB10_47") (pintype "unspecified"))
    )
    (net (code "135") (name "unconnected-(U1-PB11-Pad48)") (class "Default")
      (node (ref "U1") (pin "48") (pinfunction "PB11_48") (pintype "unspecified"))
    )
    (net (code "136") (name "unconnected-(U1-PC0-Pad15)") (class "Default")
      (node (ref "U1") (pin "15") (pinfunction "PC0_15") (pintype "unspecified"))
    )
    (net (code "137") (name "unconnected-(U1-PC1-Pad16)") (class "Default")
      (node (ref "U1") (pin "16") (pinfunction "PC1_16") (pintype "unspecified"))
    )
    (net (code "138") (name "unconnected-(U1-PC2-Pad17)") (class "Default")
      (node (ref "U1") (pin "17") (pinfunction "PC2_17") (pintype "unspecified"))
    )
    (net (code "139") (name "unconnected-(U1-PC3-Pad18)") (class "Default")
      (node (ref "U1") (pin "18") (pinfunction "PC3_18") (pintype "unspecified"))
    )
    (net (code "140") (name "unconnected-(U1-PC9-Pad66)") (class "Default")
      (node (ref "U1") (pin "66") (pinfunction "PC9_66") (pintype "unspecified"))
    )
    (net (code "141") (name "unconnected-(U1-PC13-Pad7)") (class "Default")
      (node (ref "U1") (pin "7") (pinfunction "PC13_7") (pintype "unspecified"))
    )
    (net (code "142") (name "unconnected-(U1-PD0-Pad81)") (class "Default")
      (node (ref "U1") (pin "81") (pinfunction "PD0_81") (pintype "unspecified"))
    )
    (net (code "143") (name "unconnected-(U1-PD1-Pad82)") (class "Default")
      (node (ref "U1") (pin "82") (pinfunction "PD1_82") (pintype "unspecified"))
    )
    (net (code "144") (name "unconnected-(U1-PD2-Pad83)") (class "Default")
      (node (ref "U1") (pin "83") (pinfunction "PD2_83") (pintype "unspecified"))
    )
    (net (code "145") (name "unconnected-(U1-PD3-Pad84)") (class "Default")
      (node (ref "U1") (pin "84") (pinfunction "PD3_84") (pintype "unspecified"))
    )
    (net (code "146") (name "unconnected-(U1-PD4-Pad85)") (class "Default")
      (node (ref "U1") (pin "85") (pinfunction "PD4_85") (pintype "unspecified"))
    )
    (net (code "147") (name "unconnected-(U1-PD5-Pad86)") (class "Default")
      (node (ref "U1") (pin "86") (pinfunction "PD5_86") (pintype "unspecified"))
    )
    (net (code "148") (name "unconnected-(U1-PD7-Pad88)") (class "Default")
      (node (ref "U1") (pin "88") (pinfunction "PD7_88") (pintype "unspecified"))
    )
    (net (code "149") (name "unconnected-(U1-PE1-Pad98)") (class "Default")
      (node (ref "U1") (pin "98") (pinfunction "PE1_98") (pintype "unspecified"))
    )
    (net (code "150") (name "unconnected-(U1-PE2-Pad1)") (class "Default")
      (node (ref "U1") (pin "1") (pinfunction "PE2_1") (pintype "unspecified"))
    )
    (net (code "151") (name "unconnected-(U1-PE3-Pad2)") (class "Default")
      (node (ref "U1") (pin "2") (pinfunction "PE3_2") (pintype "unspecified"))
    )
    (net (code "152") (name "unconnected-(U1-PE4-Pad3)") (class "Default")
      (node (ref "U1") (pin "3") (pinfunction "PE4_3") (pintype "unspecified"))
    )
    (net (code "153") (name "unconnected-(U1-PE5-Pad4)") (class "Default")
      (node (ref "U1") (pin "4") (pinfunction "PE5_4") (pintype "unspecified"))
    )
    (net (code "154") (name "unconnected-(U1-PE6-Pad5)") (class "Default")
      (node (ref "U1") (pin "5") (pinfunction "PE6_5") (pintype "unspecified"))
    )
    (net (code "155") (name "unconnected-(U1-PE7-Pad38)") (class "Default")
      (node (ref "U1") (pin "38") (pinfunction "PE7_38") (pintype "unspecified"))
    )
    (net (code "156") (name "unconnected-(U1-PE8-Pad39)") (class "Default")
      (node (ref "U1") (pin "39") (pinfunction "PE8_39") (pintype "unspecified"))
    )
    (net (code "157") (name "unconnected-(U1-PE10-Pad41)") (class "Default")
      (node (ref "U1") (pin "41") (pinfunction "PE10_41") (pintype "unspecified"))
    )
    (net (code "158") (name "unconnected-(U1-PE13-Pad44)") (class "Default")
      (node (ref "U1") (pin "44") (pinfunction "PE13_44") (pintype "unspecified"))
    )
    (net (code "159") (name "unconnected-(U1-PE15-Pad46)") (class "Default")
      (node (ref "U1") (pin "46") (pinfunction "PE15_46") (pintype "unspecified"))
    )
    (net (code "160") (name "unconnected-(U19-A3-Pad4)") (class "Default")
      (node (ref "U19") (pin "4") (pinfunction "A3_4") (pintype "unspecified+no_connect"))
    )
    (net (code "161") (name "unconnected-(U19-B3-Pad11)") (class "Default")
      (node (ref "U19") (pin "11") (pinfunction "B3_11") (pintype "unspecified+no_connect"))
    )
    (net (code "162") (name "unconnected-(U19-NC-Pad6)") (class "Default")
      (node (ref "U19") (pin "6") (pinfunction "NC_6") (pintype "unspecified+no_connect"))
    )
    (net (code "163") (name "unconnected-(U19-NC-Pad9)") (class "Default")
      (node (ref "U19") (pin "9") (pinfunction "NC_9") (pintype "unspecified+no_connect"))
    )
    (net (code "164") (name "unconnected-(U20-A3-Pad4)") (class "Default")
      (node (ref "U20") (pin "4") (pinfunction "A3_4") (pintype "unspecified+no_connect"))
    )
    (net (code "165") (name "unconnected-(U20-B3-Pad11)") (class "Default")
      (node (ref "U20") (pin "11") (pinfunction "B3_11") (pintype "unspecified+no_connect"))
    )
    (net (code "166") (name "unconnected-(U20-NC-Pad6)") (class "Default")
      (node (ref "U20") (pin "6") (pinfunction "NC_6") (pintype "unspecified+no_connect"))
    )
    (net (code "167") (name "unconnected-(U20-NC-Pad9)") (class "Default")
      (node (ref "U20") (pin "9") (pinfunction "NC_9") (pintype "unspecified+no_connect"))
    )
    (net (code "168") (name "unconnected-(U21-A3-Pad4)") (class "Default")
      (node (ref "U21") (pin "4") (pinfunction "A3_4") (pintype "unspecified+no_connect"))
    )
    (net (code "169") (name "unconnected-(U21-B3-Pad11)") (class "Default")
      (node (ref "U21") (pin "11") (pinfunction "B3_11") (pintype "unspecified+no_connect"))
    )
    (net (code "170") (name "unconnected-(U21-NC-Pad6)") (class "Default")
      (node (ref "U21") (pin "6") (pinfunction "NC_6") (pintype "unspecified+no_connect"))
    )
    (net (code "171") (name "unconnected-(U21-NC-Pad9)") (class "Default")
      (node (ref "U21") (pin "9") (pinfunction "NC_9") (pintype "unspecified+no_connect"))
    )
    (net (code "172") (name "unconnected-(U22-A3-Pad4)") (class "Default")
      (node (ref "U22") (pin "4") (pinfunction "A3_4") (pintype "unspecified+no_connect"))
    )
    (net (code "173") (name "unconnected-(U22-B3-Pad11)") (class "Default")
      (node (ref "U22") (pin "11") (pinfunction "B3_11") (pintype "unspecified+no_connect"))
    )
    (net (code "174") (name "unconnected-(U22-NC-Pad6)") (class "Default")
      (node (ref "U22") (pin "6") (pinfunction "NC_6") (pintype "unspecified+no_connect"))
    )
    (net (code "175") (name "unconnected-(U22-NC-Pad9)") (class "Default")
      (node (ref "U22") (pin "9") (pinfunction "NC_9") (pintype "unspecified+no_connect"))
    )
    (net (code "176") (name "unconnected-(U23-NC-Pad23)") (class "Default")
      (node (ref "U23") (pin "23") (pinfunction "NC_23") (pintype "unspecified+no_connect"))
    )
    (net (code "177") (name "unconnected-(U27-NC-Pad6)") (class "Default")
      (node (ref "U27") (pin "6") (pinfunction "NC_6") (pintype "unspecified+no_connect"))
    )
    (net (code "178") (name "unconnected-(U28-NC-Pad6)") (class "Default")
      (node (ref "U28") (pin "6") (pinfunction "NC_6") (pintype "unspecified+no_connect"))
    )
    (net (code "179") (name "unconnected-(U29-NC-Pad6)") (class "Default")
      (node (ref "U29") (pin "6") (pinfunction "NC_6") (pintype "unspecified+no_connect"))
    )
    (net (code "180") (name "unconnected-(U30-NC-Pad6)") (class "Default")
      (node (ref "U30") (pin "6") (pinfunction "NC_6") (pintype "unspecified+no_connect"))
    )
    (net (code "181") (name "unconnected-(U31-NC-Pad6)") (class "Default")
      (node (ref "U31") (pin "6") (pinfunction "NC_6") (pintype "unspecified+no_connect"))
    )
  )
)
